# dsp.net
KiCad netlist of a schematic drawn in EAGLE
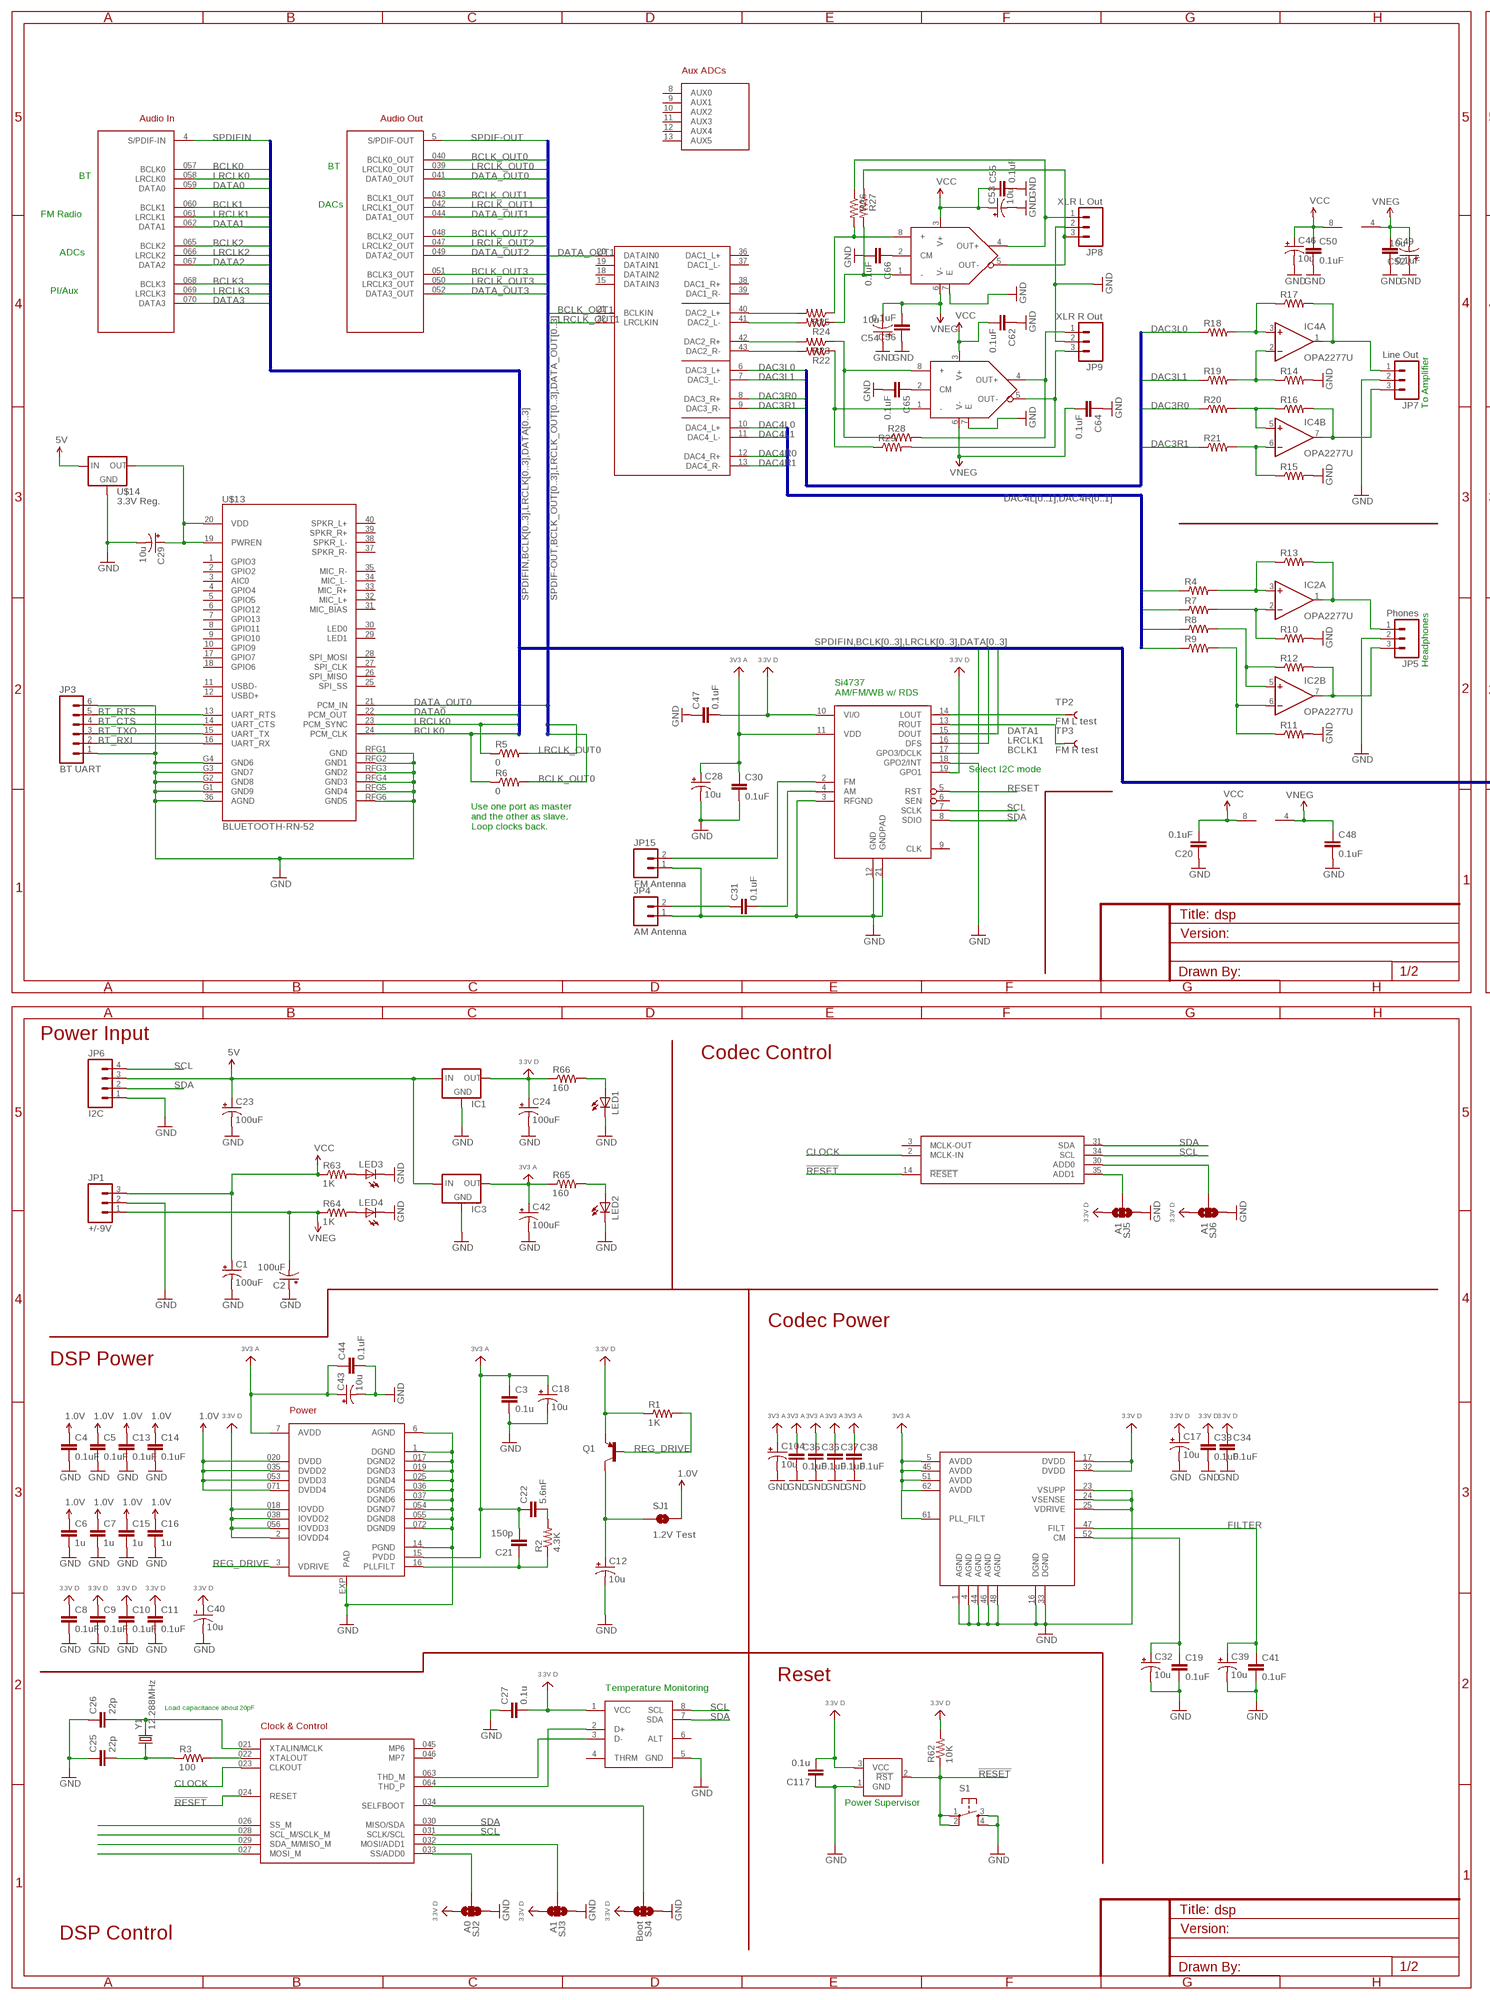
[diagram p0: schematic, sheet 1, part 1 of 2]
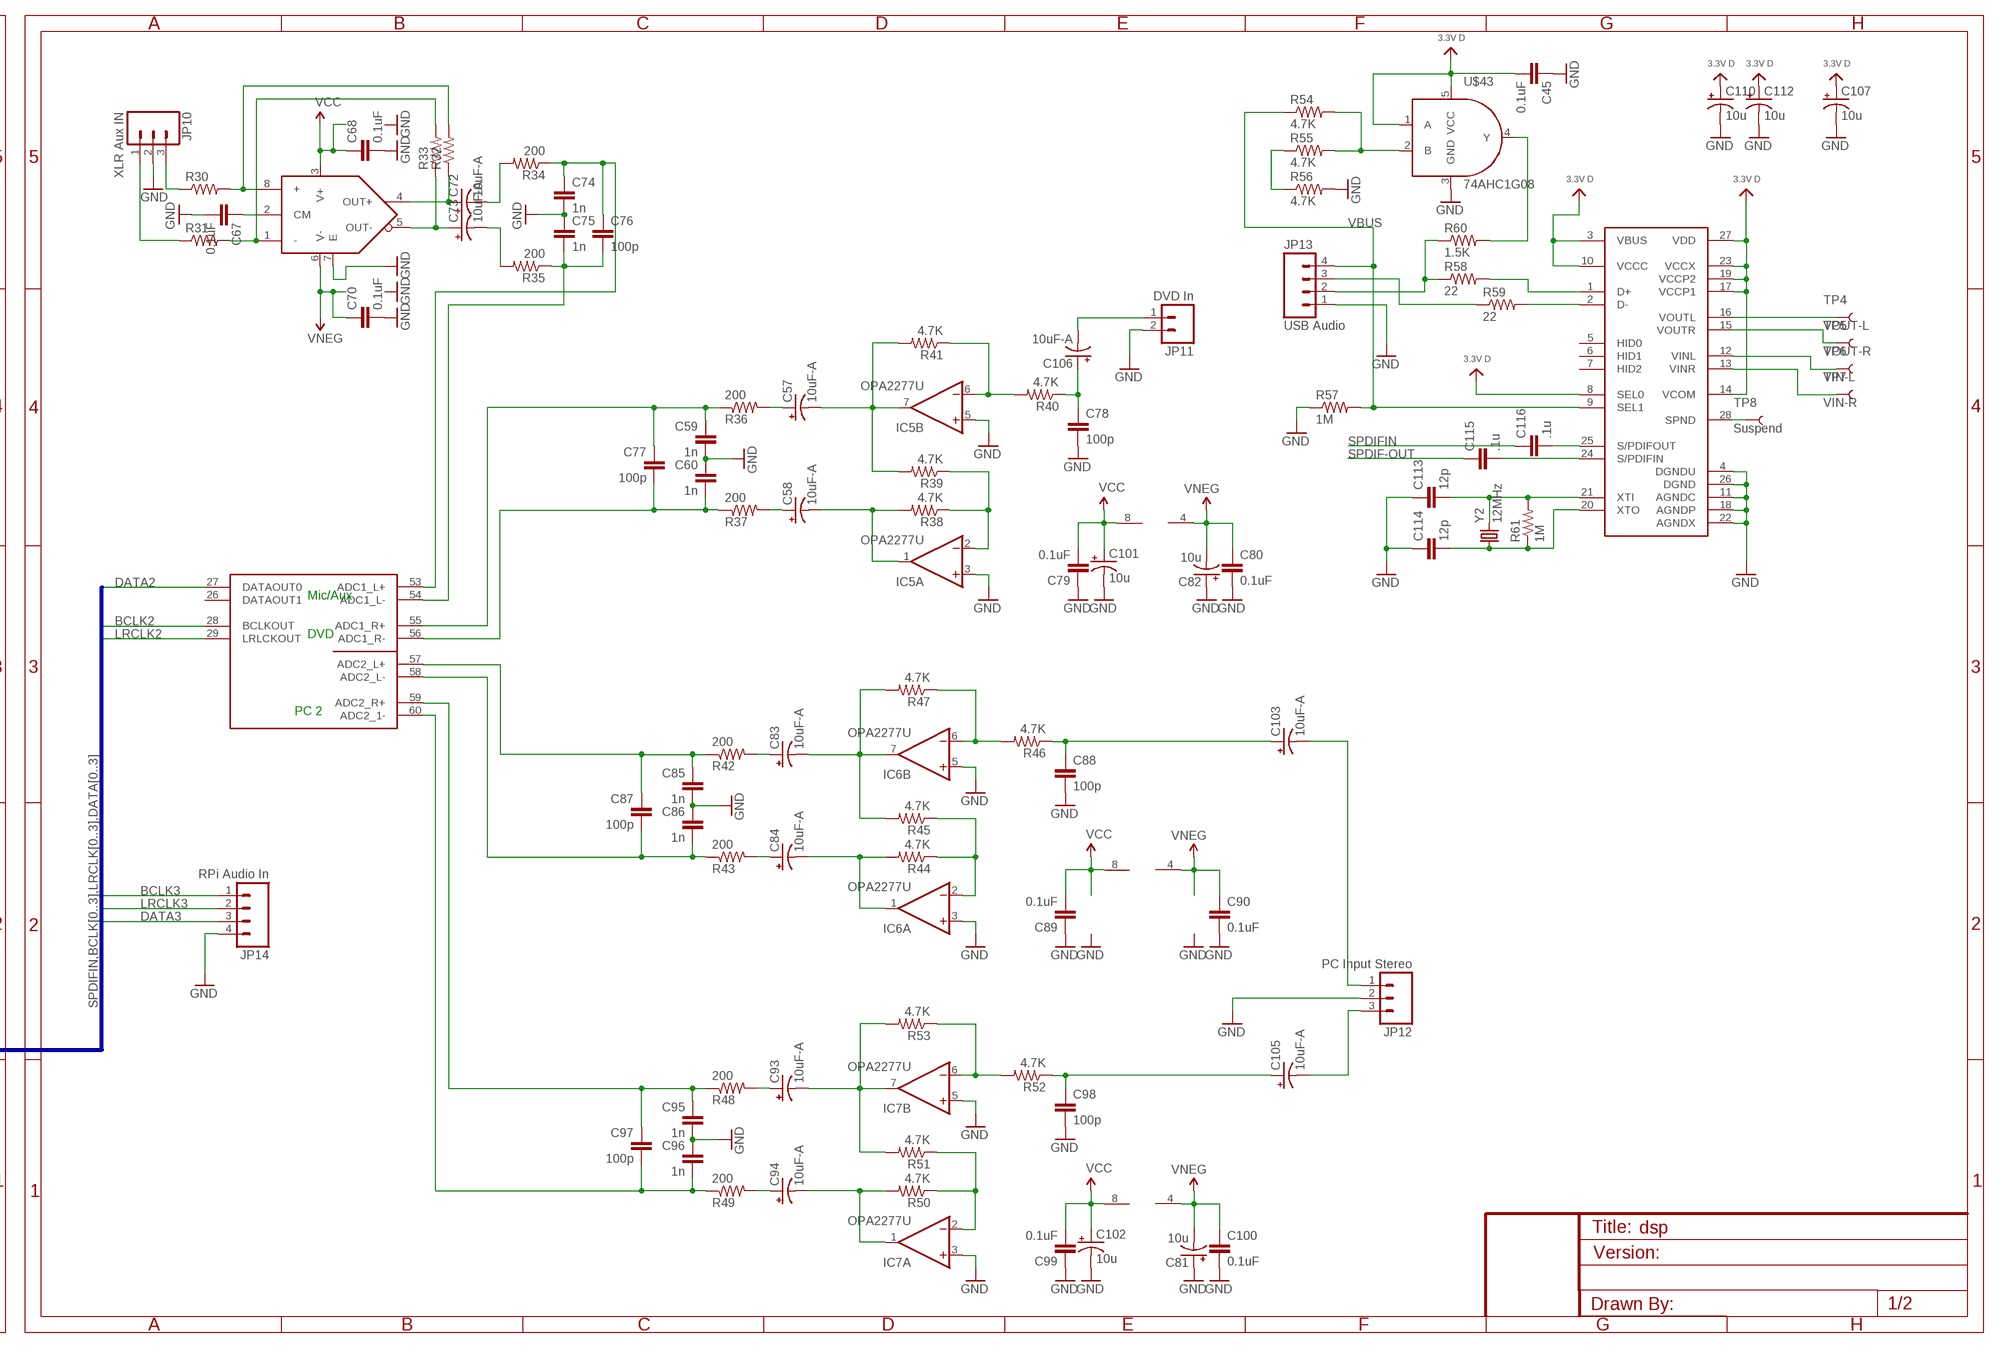
[diagram p1: schematic, sheet 1, part 2 of 2]

(export (version "E")
  (design (tool "Eeschema 10.0.6"))
  (components
    (comp (ref "C1")
      (value "100uF")
      (footprint "eagle-import:CPOL-RADIAL-100UF-25V")
      (libsource (lib "eagle-import") (part "CAP_POLPTH1"))
    )
    (comp (ref "C2")
      (value "100uF")
      (footprint "eagle-import:CPOL-RADIAL-100UF-25V")
      (libsource (lib "eagle-import") (part "CAP_POLPTH1"))
    )
    (comp (ref "C3")
      (value "0.1u")
      (footprint "eagle-import:0603-CAP")
      (libsource (lib "eagle-import") (part "CAP0603-CAP"))
    )
    (comp (ref "C4")
      (value "0.1uF")
      (footprint "eagle-import:0603-CAP")
      (libsource (lib "eagle-import") (part "CAP0603-CAP"))
    )
    (comp (ref "C5")
      (value "0.1uF")
      (footprint "eagle-import:0603-CAP")
      (libsource (lib "eagle-import") (part "CAP0603-CAP"))
    )
    (comp (ref "C6")
      (value "1u")
      (footprint "eagle-import:0603-CAP")
      (libsource (lib "eagle-import") (part "CAP0603-CAP"))
    )
    (comp (ref "C7")
      (value "1u")
      (footprint "eagle-import:0603-CAP")
      (libsource (lib "eagle-import") (part "CAP0603-CAP"))
    )
    (comp (ref "C8")
      (value "0.1uF")
      (footprint "eagle-import:0603-CAP")
      (libsource (lib "eagle-import") (part "CAP0603-CAP"))
    )
    (comp (ref "C9")
      (value "0.1uF")
      (footprint "eagle-import:0603-CAP")
      (libsource (lib "eagle-import") (part "CAP0603-CAP"))
    )
    (comp (ref "C10")
      (value "0.1uF")
      (footprint "eagle-import:0603-CAP")
      (libsource (lib "eagle-import") (part "CAP0603-CAP"))
    )
    (comp (ref "C11")
      (value "0.1uF")
      (footprint "eagle-import:0603-CAP")
      (libsource (lib "eagle-import") (part "CAP0603-CAP"))
    )
    (comp (ref "C12")
      (value "10u")
      (footprint "eagle-import:PANASONIC_B")
      (libsource (lib "eagle-import") (part "CPOL-USB"))
    )
    (comp (ref "C13")
      (value "0.1uF")
      (footprint "eagle-import:0603-CAP")
      (libsource (lib "eagle-import") (part "CAP0603-CAP"))
    )
    (comp (ref "C14")
      (value "0.1uF")
      (footprint "eagle-import:0603-CAP")
      (libsource (lib "eagle-import") (part "CAP0603-CAP"))
    )
    (comp (ref "C15")
      (value "1u")
      (footprint "eagle-import:0603-CAP")
      (libsource (lib "eagle-import") (part "CAP0603-CAP"))
    )
    (comp (ref "C16")
      (value "1u")
      (footprint "eagle-import:0603-CAP")
      (libsource (lib "eagle-import") (part "CAP0603-CAP"))
    )
    (comp (ref "C17")
      (value "10u")
      (footprint "eagle-import:PANASONIC_B")
      (libsource (lib "eagle-import") (part "CPOL-USB"))
    )
    (comp (ref "C18")
      (value "10u")
      (footprint "eagle-import:PANASONIC_B")
      (libsource (lib "eagle-import") (part "CPOL-USB"))
    )
    (comp (ref "C19")
      (value "0.1uF")
      (footprint "eagle-import:0603-CAP")
      (libsource (lib "eagle-import") (part "CAP0603-CAP"))
    )
    (comp (ref "C20")
      (value "0.1uF")
      (footprint "eagle-import:0603-CAP")
      (libsource (lib "eagle-import") (part "CAP0603-CAP"))
    )
    (comp (ref "C21")
      (value "150p")
      (footprint "eagle-import:0603-CAP")
      (libsource (lib "eagle-import") (part "CAP0603-CAP"))
    )
    (comp (ref "C22")
      (value "5.6nF")
      (footprint "eagle-import:0603-CAP")
      (libsource (lib "eagle-import") (part "CAP0603-CAP"))
    )
    (comp (ref "C23")
      (value "100uF")
      (footprint "eagle-import:CPOL-RADIAL-100UF-25V")
      (libsource (lib "eagle-import") (part "CAP_POLPTH1"))
    )
    (comp (ref "C24")
      (value "100uF")
      (footprint "eagle-import:CPOL-RADIAL-100UF-25V")
      (libsource (lib "eagle-import") (part "CAP_POLPTH1"))
    )
    (comp (ref "C25")
      (value "22p")
      (footprint "eagle-import:0603-CAP")
      (libsource (lib "eagle-import") (part "CAP0603-CAP"))
    )
    (comp (ref "C26")
      (value "22p")
      (footprint "eagle-import:0603-CAP")
      (libsource (lib "eagle-import") (part "CAP0603-CAP"))
    )
    (comp (ref "C27")
      (value "0.1u")
      (footprint "eagle-import:0603-CAP")
      (libsource (lib "eagle-import") (part "CAP0603-CAP"))
    )
    (comp (ref "C28")
      (value "10u")
      (footprint "eagle-import:PANASONIC_B")
      (libsource (lib "eagle-import") (part "CPOL-USB"))
    )
    (comp (ref "C29")
      (value "10u")
      (footprint "eagle-import:PANASONIC_B")
      (libsource (lib "eagle-import") (part "CPOL-USB"))
    )
    (comp (ref "C30")
      (value "0.1uF")
      (footprint "eagle-import:0603-CAP")
      (libsource (lib "eagle-import") (part "CAP0603-CAP"))
    )
    (comp (ref "C31")
      (value "0.1uF")
      (footprint "eagle-import:0603-CAP")
      (libsource (lib "eagle-import") (part "CAP0603-CAP"))
    )
    (comp (ref "C32")
      (value "10u")
      (footprint "eagle-import:PANASONIC_B")
      (libsource (lib "eagle-import") (part "CPOL-USB"))
    )
    (comp (ref "C33")
      (value "0.1uF")
      (footprint "eagle-import:0603-CAP")
      (libsource (lib "eagle-import") (part "CAP0603-CAP"))
    )
    (comp (ref "C34")
      (value "0.1uF")
      (footprint "eagle-import:0603-CAP")
      (libsource (lib "eagle-import") (part "CAP0603-CAP"))
    )
    (comp (ref "C35")
      (value "0.1uF")
      (footprint "eagle-import:0603-CAP")
      (libsource (lib "eagle-import") (part "CAP0603-CAP"))
    )
    (comp (ref "C36")
      (value "0.1uF")
      (footprint "eagle-import:0603-CAP")
      (libsource (lib "eagle-import") (part "CAP0603-CAP"))
    )
    (comp (ref "C37")
      (value "0.1uF")
      (footprint "eagle-import:0603-CAP")
      (libsource (lib "eagle-import") (part "CAP0603-CAP"))
    )
    (comp (ref "C38")
      (value "0.1uF")
      (footprint "eagle-import:0603-CAP")
      (libsource (lib "eagle-import") (part "CAP0603-CAP"))
    )
    (comp (ref "C39")
      (value "10u")
      (footprint "eagle-import:PANASONIC_B")
      (libsource (lib "eagle-import") (part "CPOL-USB"))
    )
    (comp (ref "C40")
      (value "10u")
      (footprint "eagle-import:PANASONIC_B")
      (libsource (lib "eagle-import") (part "CPOL-USB"))
    )
    (comp (ref "C41")
      (value "0.1uF")
      (footprint "eagle-import:0603-CAP")
      (libsource (lib "eagle-import") (part "CAP0603-CAP"))
    )
    (comp (ref "C42")
      (value "100uF")
      (footprint "eagle-import:CPOL-RADIAL-100UF-25V")
      (libsource (lib "eagle-import") (part "CAP_POLPTH1"))
    )
    (comp (ref "C43")
      (value "10u")
      (footprint "eagle-import:PANASONIC_B")
      (libsource (lib "eagle-import") (part "CPOL-USB"))
    )
    (comp (ref "C44")
      (value "0.1uF")
      (footprint "eagle-import:0603-CAP")
      (libsource (lib "eagle-import") (part "CAP0603-CAP"))
    )
    (comp (ref "C45")
      (value "0.1uF")
      (footprint "eagle-import:0603-CAP")
      (libsource (lib "eagle-import") (part "CAP0603-CAP"))
    )
    (comp (ref "C46")
      (value "10u")
      (footprint "eagle-import:PANASONIC_B")
      (libsource (lib "eagle-import") (part "CPOL-USB"))
    )
    (comp (ref "C47")
      (value "0.1uF")
      (footprint "eagle-import:0603-CAP")
      (libsource (lib "eagle-import") (part "CAP0603-CAP"))
    )
    (comp (ref "C48")
      (value "0.1uF")
      (footprint "eagle-import:0603-CAP")
      (libsource (lib "eagle-import") (part "CAP0603-CAP"))
    )
    (comp (ref "C49")
      (value "0.1uF")
      (footprint "eagle-import:0603-CAP")
      (libsource (lib "eagle-import") (part "CAP0603-CAP"))
    )
    (comp (ref "C50")
      (value "0.1uF")
      (footprint "eagle-import:0603-CAP")
      (libsource (lib "eagle-import") (part "CAP0603-CAP"))
    )
    (comp (ref "C52")
      (value "10u")
      (footprint "eagle-import:PANASONIC_B")
      (libsource (lib "eagle-import") (part "CPOL-USB"))
    )
    (comp (ref "C53")
      (value "10u")
      (footprint "eagle-import:PANASONIC_B")
      (libsource (lib "eagle-import") (part "CPOL-USB"))
    )
    (comp (ref "C54")
      (value "10u")
      (footprint "eagle-import:PANASONIC_B")
      (libsource (lib "eagle-import") (part "CPOL-USB"))
    )
    (comp (ref "C55")
      (value "0.1uF")
      (footprint "eagle-import:0603-CAP")
      (libsource (lib "eagle-import") (part "CAP0603-CAP"))
    )
    (comp (ref "C56")
      (value "0.1uF")
      (footprint "eagle-import:0603-CAP")
      (libsource (lib "eagle-import") (part "CAP0603-CAP"))
    )
    (comp (ref "C57")
      (value "10uF-A")
      (footprint "eagle-import:PANASONIC_C")
      (libsource (lib "eagle-import") (part "CAP_POLC"))
    )
    (comp (ref "C58")
      (value "10uF-A")
      (footprint "eagle-import:PANASONIC_C")
      (libsource (lib "eagle-import") (part "CAP_POLC"))
    )
    (comp (ref "C59")
      (value "1n")
      (footprint "eagle-import:0603-CAP")
      (libsource (lib "eagle-import") (part "CAP0603-CAP"))
    )
    (comp (ref "C60")
      (value "1n")
      (footprint "eagle-import:0603-CAP")
      (libsource (lib "eagle-import") (part "CAP0603-CAP"))
    )
    (comp (ref "C62")
      (value "0.1uF")
      (footprint "eagle-import:0603-CAP")
      (libsource (lib "eagle-import") (part "CAP0603-CAP"))
    )
    (comp (ref "C64")
      (value "0.1uF")
      (footprint "eagle-import:0603-CAP")
      (libsource (lib "eagle-import") (part "CAP0603-CAP"))
    )
    (comp (ref "C65")
      (value "0.1uF")
      (footprint "eagle-import:0603-CAP")
      (libsource (lib "eagle-import") (part "CAP0603-CAP"))
    )
    (comp (ref "C66")
      (value "0.1uF")
      (footprint "eagle-import:0603-CAP")
      (libsource (lib "eagle-import") (part "CAP0603-CAP"))
    )
    (comp (ref "C67")
      (value "0.1uF")
      (footprint "eagle-import:0603-CAP")
      (libsource (lib "eagle-import") (part "CAP0603-CAP"))
    )
    (comp (ref "C68")
      (value "0.1uF")
      (footprint "eagle-import:0603-CAP")
      (libsource (lib "eagle-import") (part "CAP0603-CAP"))
    )
    (comp (ref "C70")
      (value "0.1uF")
      (footprint "eagle-import:0603-CAP")
      (libsource (lib "eagle-import") (part "CAP0603-CAP"))
    )
    (comp (ref "C72")
      (value "10uF-A")
      (footprint "eagle-import:PANASONIC_C")
      (libsource (lib "eagle-import") (part "CAP_POLC"))
    )
    (comp (ref "C73")
      (value "10uF-A")
      (footprint "eagle-import:PANASONIC_C")
      (libsource (lib "eagle-import") (part "CAP_POLC"))
    )
    (comp (ref "C74")
      (value "1n")
      (footprint "eagle-import:0603-CAP")
      (libsource (lib "eagle-import") (part "CAP0603-CAP"))
    )
    (comp (ref "C75")
      (value "1n")
      (footprint "eagle-import:0603-CAP")
      (libsource (lib "eagle-import") (part "CAP0603-CAP"))
    )
    (comp (ref "C76")
      (value "100p")
      (footprint "eagle-import:0603-CAP")
      (libsource (lib "eagle-import") (part "CAP0603-CAP"))
    )
    (comp (ref "C77")
      (value "100p")
      (footprint "eagle-import:0603-CAP")
      (libsource (lib "eagle-import") (part "CAP0603-CAP"))
    )
    (comp (ref "C78")
      (value "100p")
      (footprint "eagle-import:0603-CAP")
      (libsource (lib "eagle-import") (part "CAP0603-CAP"))
    )
    (comp (ref "C79")
      (value "0.1uF")
      (footprint "eagle-import:0603-CAP")
      (libsource (lib "eagle-import") (part "CAP0603-CAP"))
    )
    (comp (ref "C80")
      (value "0.1uF")
      (footprint "eagle-import:0603-CAP")
      (libsource (lib "eagle-import") (part "CAP0603-CAP"))
    )
    (comp (ref "C81")
      (value "10u")
      (footprint "eagle-import:PANASONIC_B")
      (libsource (lib "eagle-import") (part "CPOL-USB"))
    )
    (comp (ref "C82")
      (value "10u")
      (footprint "eagle-import:PANASONIC_B")
      (libsource (lib "eagle-import") (part "CPOL-USB"))
    )
    (comp (ref "C83")
      (value "10uF-A")
      (footprint "eagle-import:PANASONIC_C")
      (libsource (lib "eagle-import") (part "CAP_POLC"))
    )
    (comp (ref "C84")
      (value "10uF-A")
      (footprint "eagle-import:PANASONIC_C")
      (libsource (lib "eagle-import") (part "CAP_POLC"))
    )
    (comp (ref "C85")
      (value "1n")
      (footprint "eagle-import:0603-CAP")
      (libsource (lib "eagle-import") (part "CAP0603-CAP"))
    )
    (comp (ref "C86")
      (value "1n")
      (footprint "eagle-import:0603-CAP")
      (libsource (lib "eagle-import") (part "CAP0603-CAP"))
    )
    (comp (ref "C87")
      (value "100p")
      (footprint "eagle-import:0603-CAP")
      (libsource (lib "eagle-import") (part "CAP0603-CAP"))
    )
    (comp (ref "C88")
      (value "100p")
      (footprint "eagle-import:0603-CAP")
      (libsource (lib "eagle-import") (part "CAP0603-CAP"))
    )
    (comp (ref "C89")
      (value "0.1uF")
      (footprint "eagle-import:0603-CAP")
      (libsource (lib "eagle-import") (part "CAP0603-CAP"))
    )
    (comp (ref "C90")
      (value "0.1uF")
      (footprint "eagle-import:0603-CAP")
      (libsource (lib "eagle-import") (part "CAP0603-CAP"))
    )
    (comp (ref "C93")
      (value "10uF-A")
      (footprint "eagle-import:PANASONIC_C")
      (libsource (lib "eagle-import") (part "CAP_POLC"))
    )
    (comp (ref "C94")
      (value "10uF-A")
      (footprint "eagle-import:PANASONIC_C")
      (libsource (lib "eagle-import") (part "CAP_POLC"))
    )
    (comp (ref "C95")
      (value "1n")
      (footprint "eagle-import:0603-CAP")
      (libsource (lib "eagle-import") (part "CAP0603-CAP"))
    )
    (comp (ref "C96")
      (value "1n")
      (footprint "eagle-import:0603-CAP")
      (libsource (lib "eagle-import") (part "CAP0603-CAP"))
    )
    (comp (ref "C97")
      (value "100p")
      (footprint "eagle-import:0603-CAP")
      (libsource (lib "eagle-import") (part "CAP0603-CAP"))
    )
    (comp (ref "C98")
      (value "100p")
      (footprint "eagle-import:0603-CAP")
      (libsource (lib "eagle-import") (part "CAP0603-CAP"))
    )
    (comp (ref "C99")
      (value "0.1uF")
      (footprint "eagle-import:0603-CAP")
      (libsource (lib "eagle-import") (part "CAP0603-CAP"))
    )
    (comp (ref "C100")
      (value "0.1uF")
      (footprint "eagle-import:0603-CAP")
      (libsource (lib "eagle-import") (part "CAP0603-CAP"))
    )
    (comp (ref "C101")
      (value "10u")
      (footprint "eagle-import:PANASONIC_B")
      (libsource (lib "eagle-import") (part "CPOL-USB"))
    )
    (comp (ref "C102")
      (value "10u")
      (footprint "eagle-import:PANASONIC_B")
      (libsource (lib "eagle-import") (part "CPOL-USB"))
    )
    (comp (ref "C103")
      (value "10uF-A")
      (footprint "eagle-import:PANASONIC_C")
      (libsource (lib "eagle-import") (part "CAP_POLC"))
    )
    (comp (ref "C104")
      (value "10u")
      (footprint "eagle-import:PANASONIC_B")
      (libsource (lib "eagle-import") (part "CPOL-USB"))
    )
    (comp (ref "C105")
      (value "10uF-A")
      (footprint "eagle-import:PANASONIC_C")
      (libsource (lib "eagle-import") (part "CAP_POLC"))
    )
    (comp (ref "C106")
      (value "10uF-A")
      (footprint "eagle-import:PANASONIC_C")
      (libsource (lib "eagle-import") (part "CAP_POLC"))
    )
    (comp (ref "C107")
      (value "10u")
      (footprint "eagle-import:PANASONIC_B")
      (libsource (lib "eagle-import") (part "CPOL-USB"))
    )
    (comp (ref "C110")
      (value "10u")
      (footprint "eagle-import:PANASONIC_B")
      (libsource (lib "eagle-import") (part "CPOL-USB"))
    )
    (comp (ref "C112")
      (value "10u")
      (footprint "eagle-import:PANASONIC_B")
      (libsource (lib "eagle-import") (part "CPOL-USB"))
    )
    (comp (ref "C113")
      (value "12p")
      (footprint "eagle-import:0603-CAP")
      (libsource (lib "eagle-import") (part "CAP0603-CAP"))
    )
    (comp (ref "C114")
      (value "12p")
      (footprint "eagle-import:0603-CAP")
      (libsource (lib "eagle-import") (part "CAP0603-CAP"))
    )
    (comp (ref "C115")
      (value ".1u")
      (footprint "eagle-import:0603-CAP")
      (libsource (lib "eagle-import") (part "CAP0603-CAP"))
    )
    (comp (ref "C116")
      (value ".1u")
      (footprint "eagle-import:0603-CAP")
      (libsource (lib "eagle-import") (part "CAP0603-CAP"))
    )
    (comp (ref "C117")
      (value "0.1u")
      (footprint "eagle-import:0603-CAP")
      (libsource (lib "eagle-import") (part "CAP0603-CAP"))
    )
    (comp (ref "IC1")
      (value "V_REG_78XXSINK")
      (footprint "eagle-import:TO220-IGO")
      (libsource (lib "eagle-import") (part "V_REG_78XXSINK"))
    )
    (comp (ref "IC2")
      (value "OPA2277U")
      (footprint "eagle-import:SO08")
      (libsource (lib "eagle-import") (part "OPA2277U"))
    )
    (comp (ref "IC3")
      (value "V_REG_78XXSINK")
      (footprint "eagle-import:TO220-IGO")
      (libsource (lib "eagle-import") (part "V_REG_78XXSINK"))
    )
    (comp (ref "IC4")
      (value "OPA2277U")
      (footprint "eagle-import:SO08")
      (libsource (lib "eagle-import") (part "OPA2277U"))
    )
    (comp (ref "IC5")
      (value "OPA2277U")
      (footprint "eagle-import:SO08")
      (libsource (lib "eagle-import") (part "OPA2277U"))
    )
    (comp (ref "IC6")
      (value "OPA2277U")
      (footprint "eagle-import:SO08")
      (libsource (lib "eagle-import") (part "OPA2277U"))
    )
    (comp (ref "IC7")
      (value "OPA2277U")
      (footprint "eagle-import:SO08")
      (libsource (lib "eagle-import") (part "OPA2277U"))
    )
    (comp (ref "JP1")
      (value "+/-9V")
      (footprint "eagle-import:MOLEX-1X3")
      (libsource (lib "eagle-import") (part "M03POLAR"))
    )
    (comp (ref "JP3")
      (value "BT UART")
      (footprint "eagle-import:MOLEX-1X6")
      (libsource (lib "eagle-import") (part "M06POLAR"))
    )
    (comp (ref "JP4")
      (value "AM Antenna")
      (footprint "eagle-import:1X02")
      (libsource (lib "eagle-import") (part "M02PTH"))
    )
    (comp (ref "JP5")
      (value "Phones")
      (footprint "eagle-import:MOLEX-1X3")
      (libsource (lib "eagle-import") (part "M03POLAR"))
    )
    (comp (ref "JP6")
      (value "I2C")
      (footprint "eagle-import:MOLEX-1X4")
      (libsource (lib "eagle-import") (part "M04POLAR"))
    )
    (comp (ref "JP7")
      (value "Line Out")
      (footprint "eagle-import:MOLEX-1X3")
      (libsource (lib "eagle-import") (part "M03POLAR"))
    )
    (comp (ref "JP8")
      (value "XLR L Out")
      (footprint "eagle-import:MOLEX-1X3")
      (libsource (lib "eagle-import") (part "M03POLAR"))
    )
    (comp (ref "JP9")
      (value "XLR R Out")
      (footprint "eagle-import:MOLEX-1X3")
      (libsource (lib "eagle-import") (part "M03POLAR"))
    )
    (comp (ref "JP10")
      (value "XLR Aux IN")
      (footprint "eagle-import:MOLEX-1X3")
      (libsource (lib "eagle-import") (part "M03POLAR"))
    )
    (comp (ref "JP11")
      (value "DVD In")
      (footprint "eagle-import:MOLEX-1X2")
      (libsource (lib "eagle-import") (part "M02POLAR"))
    )
    (comp (ref "JP12")
      (value "PC Input Stereo")
      (footprint "eagle-import:MOLEX-1X3")
      (libsource (lib "eagle-import") (part "M03POLAR"))
    )
    (comp (ref "JP13")
      (value "USB Audio")
      (footprint "eagle-import:MOLEX-1X4")
      (libsource (lib "eagle-import") (part "M04POLAR"))
    )
    (comp (ref "JP14")
      (value "RPi Audio In")
      (footprint "eagle-import:MOLEX-1X4")
      (libsource (lib "eagle-import") (part "M04POLAR"))
    )
    (comp (ref "JP15")
      (value "FM Antenna")
      (footprint "eagle-import:1X02")
      (libsource (lib "eagle-import") (part "M02PTH"))
    )
    (comp (ref "LED1")
      (value "LED1206")
      (footprint "eagle-import:LED-1206")
      (libsource (lib "eagle-import") (part "LED1206"))
    )
    (comp (ref "LED2")
      (value "LED1206")
      (footprint "eagle-import:LED-1206")
      (libsource (lib "eagle-import") (part "LED1206"))
    )
    (comp (ref "LED3")
      (value "LED1206")
      (footprint "eagle-import:LED-1206")
      (libsource (lib "eagle-import") (part "LED1206"))
    )
    (comp (ref "LED4")
      (value "LED1206")
      (footprint "eagle-import:LED-1206")
      (libsource (lib "eagle-import") (part "LED1206"))
    )
    (comp (ref "Q1")
      (value "TRANSISTOR_PNPSMD")
      (footprint "eagle-import:SOT23-3")
      (libsource (lib "eagle-import") (part "TRANSISTOR_PNPSMD"))
    )
    (comp (ref "R1")
      (value "1K")
      (footprint "eagle-import:1206")
      (libsource (lib "eagle-import") (part "RESISTOR1206"))
    )
    (comp (ref "R2")
      (value "4.3K")
      (footprint "eagle-import:1206")
      (libsource (lib "eagle-import") (part "RESISTOR1206"))
    )
    (comp (ref "R3")
      (value "100")
      (footprint "eagle-import:1206")
      (libsource (lib "eagle-import") (part "RESISTOR1206"))
    )
    (comp (ref "R4")
      (value "RESISTOR1206")
      (footprint "eagle-import:1206")
      (libsource (lib "eagle-import") (part "RESISTOR1206"))
    )
    (comp (ref "R5")
      (value "0")
      (footprint "eagle-import:1206")
      (libsource (lib "eagle-import") (part "RESISTOR1206"))
    )
    (comp (ref "R6")
      (value "0")
      (footprint "eagle-import:1206")
      (libsource (lib "eagle-import") (part "RESISTOR1206"))
    )
    (comp (ref "R7")
      (value "RESISTOR1206")
      (footprint "eagle-import:1206")
      (libsource (lib "eagle-import") (part "RESISTOR1206"))
    )
    (comp (ref "R8")
      (value "RESISTOR1206")
      (footprint "eagle-import:1206")
      (libsource (lib "eagle-import") (part "RESISTOR1206"))
    )
    (comp (ref "R9")
      (value "RESISTOR1206")
      (footprint "eagle-import:1206")
      (libsource (lib "eagle-import") (part "RESISTOR1206"))
    )
    (comp (ref "R10")
      (value "RESISTOR1206")
      (footprint "eagle-import:1206")
      (libsource (lib "eagle-import") (part "RESISTOR1206"))
    )
    (comp (ref "R11")
      (value "RESISTOR1206")
      (footprint "eagle-import:1206")
      (libsource (lib "eagle-import") (part "RESISTOR1206"))
    )
    (comp (ref "R12")
      (value "RESISTOR1206")
      (footprint "eagle-import:1206")
      (libsource (lib "eagle-import") (part "RESISTOR1206"))
    )
    (comp (ref "R13")
      (value "RESISTOR1206")
      (footprint "eagle-import:1206")
      (libsource (lib "eagle-import") (part "RESISTOR1206"))
    )
    (comp (ref "R14")
      (value "RESISTOR1206")
      (footprint "eagle-import:1206")
      (libsource (lib "eagle-import") (part "RESISTOR1206"))
    )
    (comp (ref "R15")
      (value "RESISTOR1206")
      (footprint "eagle-import:1206")
      (libsource (lib "eagle-import") (part "RESISTOR1206"))
    )
    (comp (ref "R16")
      (value "RESISTOR1206")
      (footprint "eagle-import:1206")
      (libsource (lib "eagle-import") (part "RESISTOR1206"))
    )
    (comp (ref "R17")
      (value "RESISTOR1206")
      (footprint "eagle-import:1206")
      (libsource (lib "eagle-import") (part "RESISTOR1206"))
    )
    (comp (ref "R18")
      (value "RESISTOR1206")
      (footprint "eagle-import:1206")
      (libsource (lib "eagle-import") (part "RESISTOR1206"))
    )
    (comp (ref "R19")
      (value "RESISTOR1206")
      (footprint "eagle-import:1206")
      (libsource (lib "eagle-import") (part "RESISTOR1206"))
    )
    (comp (ref "R20")
      (value "RESISTOR1206")
      (footprint "eagle-import:1206")
      (libsource (lib "eagle-import") (part "RESISTOR1206"))
    )
    (comp (ref "R21")
      (value "RESISTOR1206")
      (footprint "eagle-import:1206")
      (libsource (lib "eagle-import") (part "RESISTOR1206"))
    )
    (comp (ref "R22")
      (value "RESISTOR1206")
      (footprint "eagle-import:1206")
      (libsource (lib "eagle-import") (part "RESISTOR1206"))
    )
    (comp (ref "R23")
      (value "RESISTOR1206")
      (footprint "eagle-import:1206")
      (libsource (lib "eagle-import") (part "RESISTOR1206"))
    )
    (comp (ref "R24")
      (value "RESISTOR1206")
      (footprint "eagle-import:1206")
      (libsource (lib "eagle-import") (part "RESISTOR1206"))
    )
    (comp (ref "R25")
      (value "RESISTOR1206")
      (footprint "eagle-import:1206")
      (libsource (lib "eagle-import") (part "RESISTOR1206"))
    )
    (comp (ref "R26")
      (value "RESISTOR1206")
      (footprint "eagle-import:1206")
      (libsource (lib "eagle-import") (part "RESISTOR1206"))
    )
    (comp (ref "R27")
      (value "RESISTOR1206")
      (footprint "eagle-import:1206")
      (libsource (lib "eagle-import") (part "RESISTOR1206"))
    )
    (comp (ref "R28")
      (value "RESISTOR1206")
      (footprint "eagle-import:1206")
      (libsource (lib "eagle-import") (part "RESISTOR1206"))
    )
    (comp (ref "R29")
      (value "RESISTOR1206")
      (footprint "eagle-import:1206")
      (libsource (lib "eagle-import") (part "RESISTOR1206"))
    )
    (comp (ref "R30")
      (value "RESISTOR1206")
      (footprint "eagle-import:1206")
      (libsource (lib "eagle-import") (part "RESISTOR1206"))
    )
    (comp (ref "R31")
      (value "RESISTOR1206")
      (footprint "eagle-import:1206")
      (libsource (lib "eagle-import") (part "RESISTOR1206"))
    )
    (comp (ref "R32")
      (value "RESISTOR1206")
      (footprint "eagle-import:1206")
      (libsource (lib "eagle-import") (part "RESISTOR1206"))
    )
    (comp (ref "R33")
      (value "RESISTOR1206")
      (footprint "eagle-import:1206")
      (libsource (lib "eagle-import") (part "RESISTOR1206"))
    )
    (comp (ref "R34")
      (value "200")
      (footprint "eagle-import:1206")
      (libsource (lib "eagle-import") (part "RESISTOR1206"))
    )
    (comp (ref "R35")
      (value "200")
      (footprint "eagle-import:1206")
      (libsource (lib "eagle-import") (part "RESISTOR1206"))
    )
    (comp (ref "R36")
      (value "200")
      (footprint "eagle-import:1206")
      (libsource (lib "eagle-import") (part "RESISTOR1206"))
    )
    (comp (ref "R37")
      (value "200")
      (footprint "eagle-import:1206")
      (libsource (lib "eagle-import") (part "RESISTOR1206"))
    )
    (comp (ref "R38")
      (value "4.7K")
      (footprint "eagle-import:1206")
      (libsource (lib "eagle-import") (part "RESISTOR1206"))
    )
    (comp (ref "R39")
      (value "4.7K")
      (footprint "eagle-import:1206")
      (libsource (lib "eagle-import") (part "RESISTOR1206"))
    )
    (comp (ref "R40")
      (value "4.7K")
      (footprint "eagle-import:1206")
      (libsource (lib "eagle-import") (part "RESISTOR1206"))
    )
    (comp (ref "R41")
      (value "4.7K")
      (footprint "eagle-import:1206")
      (libsource (lib "eagle-import") (part "RESISTOR1206"))
    )
    (comp (ref "R42")
      (value "200")
      (footprint "eagle-import:1206")
      (libsource (lib "eagle-import") (part "RESISTOR1206"))
    )
    (comp (ref "R43")
      (value "200")
      (footprint "eagle-import:1206")
      (libsource (lib "eagle-import") (part "RESISTOR1206"))
    )
    (comp (ref "R44")
      (value "4.7K")
      (footprint "eagle-import:1206")
      (libsource (lib "eagle-import") (part "RESISTOR1206"))
    )
    (comp (ref "R45")
      (value "4.7K")
      (footprint "eagle-import:1206")
      (libsource (lib "eagle-import") (part "RESISTOR1206"))
    )
    (comp (ref "R46")
      (value "4.7K")
      (footprint "eagle-import:1206")
      (libsource (lib "eagle-import") (part "RESISTOR1206"))
    )
    (comp (ref "R47")
      (value "4.7K")
      (footprint "eagle-import:1206")
      (libsource (lib "eagle-import") (part "RESISTOR1206"))
    )
    (comp (ref "R48")
      (value "200")
      (footprint "eagle-import:1206")
      (libsource (lib "eagle-import") (part "RESISTOR1206"))
    )
    (comp (ref "R49")
      (value "200")
      (footprint "eagle-import:1206")
      (libsource (lib "eagle-import") (part "RESISTOR1206"))
    )
    (comp (ref "R50")
      (value "4.7K")
      (footprint "eagle-import:1206")
      (libsource (lib "eagle-import") (part "RESISTOR1206"))
    )
    (comp (ref "R51")
      (value "4.7K")
      (footprint "eagle-import:1206")
      (libsource (lib "eagle-import") (part "RESISTOR1206"))
    )
    (comp (ref "R52")
      (value "4.7K")
      (footprint "eagle-import:1206")
      (libsource (lib "eagle-import") (part "RESISTOR1206"))
    )
    (comp (ref "R53")
      (value "4.7K")
      (footprint "eagle-import:1206")
      (libsource (lib "eagle-import") (part "RESISTOR1206"))
    )
    (comp (ref "R54")
      (value "4.7K")
      (footprint "eagle-import:1206")
      (libsource (lib "eagle-import") (part "RESISTOR1206"))
    )
    (comp (ref "R55")
      (value "4.7K")
      (footprint "eagle-import:1206")
      (libsource (lib "eagle-import") (part "RESISTOR1206"))
    )
    (comp (ref "R56")
      (value "4.7K")
      (footprint "eagle-import:1206")
      (libsource (lib "eagle-import") (part "RESISTOR1206"))
    )
    (comp (ref "R57")
      (value "1M")
      (footprint "eagle-import:1206")
      (libsource (lib "eagle-import") (part "RESISTOR1206"))
    )
    (comp (ref "R58")
      (value "22")
      (footprint "eagle-import:1206")
      (libsource (lib "eagle-import") (part "RESISTOR1206"))
    )
    (comp (ref "R59")
      (value "22")
      (footprint "eagle-import:1206")
      (libsource (lib "eagle-import") (part "RESISTOR1206"))
    )
    (comp (ref "R60")
      (value "1.5K")
      (footprint "eagle-import:1206")
      (libsource (lib "eagle-import") (part "RESISTOR1206"))
    )
    (comp (ref "R61")
      (value "1M")
      (footprint "eagle-import:1206")
      (libsource (lib "eagle-import") (part "RESISTOR1206"))
    )
    (comp (ref "R62")
      (value "10K")
      (footprint "eagle-import:1206")
      (libsource (lib "eagle-import") (part "RESISTOR1206"))
    )
    (comp (ref "R63")
      (value "1K")
      (footprint "eagle-import:1206")
      (libsource (lib "eagle-import") (part "RESISTOR1206"))
    )
    (comp (ref "R64")
      (value "1K")
      (footprint "eagle-import:1206")
      (libsource (lib "eagle-import") (part "RESISTOR1206"))
    )
    (comp (ref "R65")
      (value "160")
      (footprint "eagle-import:1206")
      (libsource (lib "eagle-import") (part "RESISTOR1206"))
    )
    (comp (ref "R66")
      (value "160")
      (footprint "eagle-import:1206")
      (libsource (lib "eagle-import") (part "RESISTOR1206"))
    )
    (comp (ref "S1")
      (value "TAC_SWITCHPTH")
      (footprint "eagle-import:TACTILE-PTH")
      (libsource (lib "eagle-import") (part "TAC_SWITCHPTH"))
    )
    (comp (ref "SJ1")
      (value "1.2V Test")
      (footprint "eagle-import:SJ_2S-NO")
      (libsource (lib "eagle-import") (part "SOLDERJUMPERNO"))
    )
    (comp (ref "SJ2")
      (value "A0")
      (footprint "eagle-import:SJ_3")
      (libsource (lib "eagle-import") (part "SOLDERJUMPER_2WAYS"))
    )
    (comp (ref "SJ3")
      (value "A1")
      (footprint "eagle-import:SJ_3")
      (libsource (lib "eagle-import") (part "SOLDERJUMPER_2WAYS"))
    )
    (comp (ref "SJ4")
      (value "Boot")
      (footprint "eagle-import:SJ_3")
      (libsource (lib "eagle-import") (part "SOLDERJUMPER_2WAYS"))
    )
    (comp (ref "SJ5")
      (value "A1")
      (footprint "eagle-import:SJ_3")
      (libsource (lib "eagle-import") (part "SOLDERJUMPER_2WAYS"))
    )
    (comp (ref "SJ6")
      (value "A1")
      (footprint "eagle-import:SJ_3")
      (libsource (lib "eagle-import") (part "SOLDERJUMPER_2WAYS"))
    )
    (comp (ref "TP2")
      (value "FM L test")
      (footprint "eagle-import:PAD.03X.03")
      (libsource (lib "eagle-import") (part "TEST-POINT3"))
    )
    (comp (ref "TP3")
      (value "FM R test")
      (footprint "eagle-import:PAD.03X.03")
      (libsource (lib "eagle-import") (part "TEST-POINT3"))
    )
    (comp (ref "TP4")
      (value "VOUT-L")
      (footprint "eagle-import:PAD.03X.03")
      (libsource (lib "eagle-import") (part "TEST-POINT3"))
    )
    (comp (ref "TP5")
      (value "VOUT-R")
      (footprint "eagle-import:PAD.03X.03")
      (libsource (lib "eagle-import") (part "TEST-POINT3"))
    )
    (comp (ref "TP6")
      (value "VIN-L")
      (footprint "eagle-import:PAD.03X.03")
      (libsource (lib "eagle-import") (part "TEST-POINT3"))
    )
    (comp (ref "TP7")
      (value "VIN-R")
      (footprint "eagle-import:PAD.03X.03")
      (libsource (lib "eagle-import") (part "TEST-POINT3"))
    )
    (comp (ref "TP8")
      (value "Suspend")
      (footprint "eagle-import:PAD.03X.03")
      (libsource (lib "eagle-import") (part "TEST-POINT3"))
    )
    (comp (ref "U$1")
      (value "ADAU1451")
      (footprint "eagle-import:LFCSP-72")
      (libsource (lib "eagle-import") (part "ADAU1451"))
    )
    (comp (ref "U$8")
      (value "ADM1032")
      (footprint "eagle-import:MSOP-8")
      (libsource (lib "eagle-import") (part "ADM1032"))
    )
    (comp (ref "U$13")
      (value "BLUETOOTH-RN-52")
      (footprint "eagle-import:RN-52")
      (libsource (lib "eagle-import") (part "BLUETOOTH-RN-52"))
    )
    (comp (ref "U$14")
      (value "3.3V Reg.")
      (footprint "eagle-import:SOT223")
      (libsource (lib "eagle-import") (part "V_REG_MIC2920"))
    )
    (comp (ref "U$15")
      (value "SI4736/37/38/39")
      (footprint "eagle-import:QFN-16")
      (libsource (lib "eagle-import") (part "SI4736/37/38/39"))
    )
    (comp (ref "U$17")
      (value "AD1937")
      (footprint "eagle-import:LQFP-64")
      (libsource (lib "eagle-import") (part "AD1937"))
    )
    (comp (ref "U$35")
      (value "LME49724")
      (footprint "eagle-import:SOIC-8")
      (libsource (lib "eagle-import") (part "LME49724"))
    )
    (comp (ref "U$38")
      (value "LME49724")
      (footprint "eagle-import:SOIC-8")
      (libsource (lib "eagle-import") (part "LME49724"))
    )
    (comp (ref "U$39")
      (value "LME49724")
      (footprint "eagle-import:SOIC-8")
      (libsource (lib "eagle-import") (part "LME49724"))
    )
    (comp (ref "U$40")
      (value "PCM2903")
      (footprint "eagle-import:SSOP-28")
      (libsource (lib "eagle-import") (part "PCM2903"))
    )
    (comp (ref "U$43")
      (value "74AHC1G08")
      (footprint "eagle-import:SOT23-5")
      (libsource (lib "eagle-import") (part "74AHC1G08"))
    )
    (comp (ref "U$52")
      (value "TLV803")
      (footprint "eagle-import:SOT23")
      (libsource (lib "eagle-import") (part "TLV803"))
    )
    (comp (ref "Y1")
      (value "12.288MHz")
      (footprint "eagle-import:HC49U-V")
      (libsource (lib "eagle-import") (part "CRYSTALHC49UV"))
    )
    (comp (ref "Y2")
      (value "12MHz")
      (footprint "eagle-import:HC49U-V")
      (libsource (lib "eagle-import") (part "CRYSTALHC49UV"))
    )
  )
  (nets
    (net (code "4") (name "1.0V") (class "Default")
      (node (ref "C13") (pin "1") (pinfunction "1_1") (pintype "passive"))
      (node (ref "C14") (pin "1") (pinfunction "1_1") (pintype "passive"))
      (node (ref "C15") (pin "1") (pinfunction "1_1") (pintype "passive"))
      (node (ref "C16") (pin "1") (pinfunction "1_1") (pintype "passive"))
      (node (ref "C4") (pin "1") (pinfunction "1_1") (pintype "passive"))
      (node (ref "C5") (pin "1") (pinfunction "1_1") (pintype "passive"))
      (node (ref "C6") (pin "1") (pinfunction "1_1") (pintype "passive"))
      (node (ref "C7") (pin "1") (pinfunction "1_1") (pintype "passive"))
      (node (ref "SJ1") (pin "2") (pinfunction "2_2") (pintype "passive"))
      (node (ref "U$1") (pin "020") (pinfunction "DVDD_020") (pintype "bidirectional"))
      (node (ref "U$1") (pin "035") (pinfunction "DVDD2_035") (pintype "bidirectional"))
      (node (ref "U$1") (pin "053") (pinfunction "DVDD3_053") (pintype "bidirectional"))
      (node (ref "U$1") (pin "071") (pinfunction "DVDD4_071") (pintype "bidirectional"))
    )
    (net (code "5") (name "3.3V_A") (class "Default")
      (node (ref "C104") (pin "+") (pinfunction "+_+") (pintype "passive"))
      (node (ref "C18") (pin "+") (pinfunction "+_+") (pintype "passive"))
      (node (ref "C21") (pin "2") (pinfunction "2_2") (pintype "passive"))
      (node (ref "C22") (pin "1") (pinfunction "1_1") (pintype "passive"))
      (node (ref "C28") (pin "+") (pinfunction "+_+") (pintype "passive"))
      (node (ref "C3") (pin "1") (pinfunction "1_1") (pintype "passive"))
      (node (ref "C30") (pin "1") (pinfunction "1_1") (pintype "passive"))
      (node (ref "C35") (pin "1") (pinfunction "1_1") (pintype "passive"))
      (node (ref "C36") (pin "1") (pinfunction "1_1") (pintype "passive"))
      (node (ref "C37") (pin "1") (pinfunction "1_1") (pintype "passive"))
      (node (ref "C38") (pin "1") (pinfunction "1_1") (pintype "passive"))
      (node (ref "C42") (pin "1") (pinfunction "+_1") (pintype "passive"))
      (node (ref "C43") (pin "+") (pinfunction "+_+") (pintype "passive"))
      (node (ref "C44") (pin "1") (pinfunction "1_1") (pintype "passive"))
      (node (ref "IC3") (pin "OUT") (pinfunction "OUT_OUT") (pintype "output"))
      (node (ref "R65") (pin "1") (pinfunction "1_1") (pintype "passive"))
      (node (ref "U$1") (pin "15") (pinfunction "PVDD_15") (pintype "bidirectional"))
      (node (ref "U$1") (pin "7") (pinfunction "AVDD_7") (pintype "bidirectional"))
      (node (ref "U$15") (pin "11") (pinfunction "VDD_11") (pintype "bidirectional"))
      (node (ref "U$17") (pin "45") (pinfunction "AVDD_45") (pintype "bidirectional"))
      (node (ref "U$17") (pin "5") (pinfunction "AVDD_5") (pintype "bidirectional"))
      (node (ref "U$17") (pin "51") (pinfunction "AVDD_51") (pintype "bidirectional"))
      (node (ref "U$17") (pin "61") (pinfunction "PLL_FILT_61") (pintype "bidirectional"))
      (node (ref "U$17") (pin "62") (pinfunction "AVDD_62") (pintype "bidirectional"))
    )
    (net (code "6") (name "3V3_D") (class "Default")
      (node (ref "C10") (pin "1") (pinfunction "1_1") (pintype "passive"))
      (node (ref "C107") (pin "+") (pinfunction "+_+") (pintype "passive"))
      (node (ref "C11") (pin "1") (pinfunction "1_1") (pintype "passive"))
      (node (ref "C110") (pin "+") (pinfunction "+_+") (pintype "passive"))
      (node (ref "C112") (pin "+") (pinfunction "+_+") (pintype "passive"))
      (node (ref "C117") (pin "2") (pinfunction "2_2") (pintype "passive"))
      (node (ref "C17") (pin "+") (pinfunction "+_+") (pintype "passive"))
      (node (ref "C24") (pin "1") (pinfunction "+_1") (pintype "passive"))
      (node (ref "C27") (pin "2") (pinfunction "2_2") (pintype "passive"))
      (node (ref "C33") (pin "1") (pinfunction "1_1") (pintype "passive"))
      (node (ref "C34") (pin "1") (pinfunction "1_1") (pintype "passive"))
      (node (ref "C40") (pin "+") (pinfunction "+_+") (pintype "passive"))
      (node (ref "C45") (pin "2") (pinfunction "2_2") (pintype "passive"))
      (node (ref "C47") (pin "2") (pinfunction "2_2") (pintype "passive"))
      (node (ref "C8") (pin "1") (pinfunction "1_1") (pintype "passive"))
      (node (ref "C9") (pin "1") (pinfunction "1_1") (pintype "passive"))
      (node (ref "IC1") (pin "OUT") (pinfunction "OUT_OUT") (pintype "output"))
      (node (ref "Q1") (pin "2") (pinfunction "E_2") (pintype "passive"))
      (node (ref "R1") (pin "1") (pinfunction "1_1") (pintype "passive"))
      (node (ref "R62") (pin "2") (pinfunction "2_2") (pintype "passive"))
      (node (ref "R66") (pin "1") (pinfunction "1_1") (pintype "passive"))
      (node (ref "SJ2") (pin "3") (pinfunction "3_3") (pintype "passive"))
      (node (ref "SJ3") (pin "3") (pinfunction "3_3") (pintype "passive"))
      (node (ref "SJ4") (pin "3") (pinfunction "3_3") (pintype "passive"))
      (node (ref "SJ5") (pin "3") (pinfunction "3_3") (pintype "passive"))
      (node (ref "SJ6") (pin "3") (pinfunction "3_3") (pintype "passive"))
      (node (ref "U$1") (pin "018") (pinfunction "IOVDD_018") (pintype "bidirectional"))
      (node (ref "U$1") (pin "038") (pinfunction "IOVDD2_038") (pintype "bidirectional"))
      (node (ref "U$1") (pin "056") (pinfunction "IOVDD3_056") (pintype "bidirectional"))
      (node (ref "U$1") (pin "2") (pinfunction "IOVDD4_2") (pintype "bidirectional"))
      (node (ref "U$15") (pin "10") (pinfunction "VI/O_10") (pintype "bidirectional"))
      (node (ref "U$15") (pin "19") (pinfunction "GPO1_19") (pintype "bidirectional"))
      (node (ref "U$17") (pin "17") (pinfunction "DVDD_17") (pintype "bidirectional"))
      (node (ref "U$17") (pin "32") (pinfunction "DVDD_32") (pintype "bidirectional"))
      (node (ref "U$40") (pin "10") (pinfunction "VCCC_10") (pintype "bidirectional"))
      (node (ref "U$40") (pin "14") (pinfunction "VCOM_14") (pintype "bidirectional"))
      (node (ref "U$40") (pin "17") (pinfunction "VCCP1_17") (pintype "bidirectional"))
      (node (ref "U$40") (pin "19") (pinfunction "VCCP2_19") (pintype "bidirectional"))
      (node (ref "U$40") (pin "23") (pinfunction "VCCX_23") (pintype "bidirectional"))
      (node (ref "U$40") (pin "27") (pinfunction "VDD_27") (pintype "bidirectional"))
      (node (ref "U$40") (pin "3") (pinfunction "VBUS_3") (pintype "bidirectional"))
      (node (ref "U$40") (pin "8") (pinfunction "SEL0_8") (pintype "bidirectional"))
      (node (ref "U$43") (pin "1") (pinfunction "A_1") (pintype "bidirectional"))
      (node (ref "U$43") (pin "5") (pinfunction "VCC_5") (pintype "bidirectional"))
      (node (ref "U$52") (pin "3") (pinfunction "VCC_3") (pintype "bidirectional"))
      (node (ref "U$8") (pin "1") (pinfunction "VCC_1") (pintype "bidirectional"))
    )
    (net (code "7") (name "5V") (class "Default")
      (node (ref "C23") (pin "1") (pinfunction "+_1") (pintype "passive"))
      (node (ref "IC1") (pin "IN") (pinfunction "IN_IN") (pintype "input"))
      (node (ref "IC3") (pin "IN") (pinfunction "IN_IN") (pintype "input"))
      (node (ref "JP6") (pin "3") (pinfunction "3_3") (pintype "passive"))
      (node (ref "U$14") (pin "1") (pinfunction "IN_1") (pintype "input"))
    )
    (net (code "8") (name "BCLK0") (class "Default")
      (node (ref "R6") (pin "1") (pinfunction "1_1") (pintype "passive"))
      (node (ref "U$1") (pin "057") (pinfunction "BCLK0_057") (pintype "bidirectional"))
      (node (ref "U$13") (pin "24") (pinfunction "PCM_CLK_24") (pintype "bidirectional"))
    )
    (net (code "9") (name "BCLK1") (class "Default")
      (node (ref "U$1") (pin "060") (pinfunction "BCLK1_060") (pintype "bidirectional"))
      (node (ref "U$15") (pin "17") (pinfunction "GPO3/DCLK_17") (pintype "bidirectional"))
    )
    (net (code "10") (name "BCLK2") (class "Default")
      (node (ref "U$1") (pin "065") (pinfunction "BCLK2_065") (pintype "bidirectional"))
      (node (ref "U$17") (pin "28") (pinfunction "BCLKOUT_28") (pintype "bidirectional"))
    )
    (net (code "11") (name "BCLK3") (class "Default")
      (node (ref "JP14") (pin "1") (pinfunction "1_1") (pintype "passive"))
      (node (ref "U$1") (pin "068") (pinfunction "BCLK3_068") (pintype "bidirectional"))
    )
    (net (code "12") (name "BCLK_OUT0") (class "Default")
      (node (ref "R6") (pin "2") (pinfunction "2_2") (pintype "passive"))
      (node (ref "U$1") (pin "040") (pinfunction "BCLK0_OUT_040") (pintype "bidirectional"))
    )
    (net (code "13") (name "BCLK_OUT1") (class "Default")
      (node (ref "U$1") (pin "043") (pinfunction "BCLK1_OUT_043") (pintype "bidirectional"))
      (node (ref "U$17") (pin "21") (pinfunction "BCLKIN_21") (pintype "bidirectional"))
    )
    (net (code "14") (name "BCLK_OUT2") (class "Default")
      (node (ref "U$1") (pin "048") (pinfunction "BCLK2_OUT_048") (pintype "bidirectional"))
    )
    (net (code "15") (name "BCLK_OUT3") (class "Default")
      (node (ref "U$1") (pin "051") (pinfunction "BCLK3_OUT_051") (pintype "bidirectional"))
    )
    (net (code "16") (name "BT_CTS") (class "Default")
      (node (ref "JP3") (pin "4") (pinfunction "4_4") (pintype "passive"))
      (node (ref "U$13") (pin "14") (pinfunction "UART_CTS_14") (pintype "bidirectional"))
    )
    (net (code "17") (name "BT_RTS") (class "Default")
      (node (ref "JP3") (pin "5") (pinfunction "5_5") (pintype "passive"))
      (node (ref "U$13") (pin "13") (pinfunction "UART_RTS_13") (pintype "bidirectional"))
    )
    (net (code "18") (name "BT_RXI") (class "Default")
      (node (ref "JP3") (pin "2") (pinfunction "2_2") (pintype "passive"))
      (node (ref "U$13") (pin "16") (pinfunction "UART_RX_16") (pintype "bidirectional"))
    )
    (net (code "19") (name "BT_TXO") (class "Default")
      (node (ref "JP3") (pin "3") (pinfunction "3_3") (pintype "passive"))
      (node (ref "U$13") (pin "15") (pinfunction "UART_TX_15") (pintype "bidirectional"))
    )
    (net (code "20") (name "CLOCK") (class "Default")
      (node (ref "U$1") (pin "023") (pinfunction "CLKOUT_023") (pintype "bidirectional"))
      (node (ref "U$17") (pin "2") (pinfunction "MCLK-IN_2") (pintype "bidirectional"))
    )
    (net (code "21") (name "DAC3L0") (class "Default")
      (node (ref "R18") (pin "1") (pinfunction "1_1") (pintype "passive"))
      (node (ref "U$17") (pin "6") (pinfunction "DAC3_L+_6") (pintype "bidirectional"))
    )
    (net (code "22") (name "DAC3L1") (class "Default")
      (node (ref "R19") (pin "1") (pinfunction "1_1") (pintype "passive"))
      (node (ref "U$17") (pin "7") (pinfunction "DAC3_L-_7") (pintype "bidirectional"))
    )
    (net (code "23") (name "DAC3R0") (class "Default")
      (node (ref "R20") (pin "1") (pinfunction "1_1") (pintype "passive"))
      (node (ref "U$17") (pin "8") (pinfunction "DAC3_R+_8") (pintype "bidirectional"))
    )
    (net (code "24") (name "DAC3R1") (class "Default")
      (node (ref "R21") (pin "1") (pinfunction "1_1") (pintype "passive"))
      (node (ref "U$17") (pin "9") (pinfunction "DAC3_R-_9") (pintype "bidirectional"))
    )
    (net (code "25") (name "DAC4L0") (class "Default")
      (node (ref "R4") (pin "1") (pinfunction "1_1") (pintype "passive"))
      (node (ref "U$17") (pin "10") (pinfunction "DAC4_L+_10") (pintype "bidirectional"))
    )
    (net (code "26") (name "DAC4L1") (class "Default")
      (node (ref "R7") (pin "1") (pinfunction "1_1") (pintype "passive"))
      (node (ref "U$17") (pin "11") (pinfunction "DAC4_L-_11") (pintype "bidirectional"))
    )
    (net (code "27") (name "DAC4R0") (class "Default")
      (node (ref "R8") (pin "1") (pinfunction "1_1") (pintype "passive"))
      (node (ref "U$17") (pin "12") (pinfunction "DAC4_R+_12") (pintype "bidirectional"))
    )
    (net (code "28") (name "DAC4R1") (class "Default")
      (node (ref "R9") (pin "1") (pinfunction "1_1") (pintype "passive"))
      (node (ref "U$17") (pin "13") (pinfunction "DAC4_R-_13") (pintype "bidirectional"))
    )
    (net (code "29") (name "DATA0") (class "Default")
      (node (ref "U$1") (pin "059") (pinfunction "DATA0_059") (pintype "bidirectional"))
      (node (ref "U$13") (pin "22") (pinfunction "PCM_OUT_22") (pintype "bidirectional"))
    )
    (net (code "30") (name "DATA1") (class "Default")
      (node (ref "U$1") (pin "062") (pinfunction "DATA1_062") (pintype "bidirectional"))
      (node (ref "U$15") (pin "15") (pinfunction "DOUT_15") (pintype "bidirectional"))
    )
    (net (code "31") (name "DATA2") (class "Default")
      (node (ref "U$1") (pin "067") (pinfunction "DATA2_067") (pintype "bidirectional"))
      (node (ref "U$17") (pin "27") (pinfunction "DATAOUT0_27") (pintype "bidirectional"))
    )
    (net (code "32") (name "DATA3") (class "Default")
      (node (ref "JP14") (pin "3") (pinfunction "3_3") (pintype "passive"))
      (node (ref "U$1") (pin "070") (pinfunction "DATA3_070") (pintype "bidirectional"))
    )
    (net (code "33") (name "DATA_OUT0") (class "Default")
      (node (ref "U$1") (pin "041") (pinfunction "DATA0_OUT_041") (pintype "bidirectional"))
      (node (ref "U$13") (pin "21") (pinfunction "PCM_IN_21") (pintype "bidirectional"))
    )
    (net (code "34") (name "DATA_OUT1") (class "Default")
      (node (ref "U$1") (pin "044") (pinfunction "DATA1_OUT_044") (pintype "bidirectional"))
      (node (ref "U$17") (pin "20") (pinfunction "DATAIN0_20") (pintype "bidirectional"))
    )
    (net (code "35") (name "DATA_OUT2") (class "Default")
      (node (ref "U$1") (pin "049") (pinfunction "DATA2_OUT_049") (pintype "bidirectional"))
    )
    (net (code "36") (name "DATA_OUT3") (class "Default")
      (node (ref "U$1") (pin "052") (pinfunction "DATA3_OUT_052") (pintype "bidirectional"))
    )
    (net (code "37") (name "FILTER") (class "Default")
      (node (ref "C39") (pin "+") (pinfunction "+_+") (pintype "passive"))
      (node (ref "C41") (pin "1") (pinfunction "1_1") (pintype "passive"))
      (node (ref "U$17") (pin "47") (pinfunction "FILT_47") (pintype "bidirectional"))
    )
    (net (code "38") (name "GND") (class "Default")
      (node (ref "C1") (pin "2") (pinfunction "-_2") (pintype "passive"))
      (node (ref "C10") (pin "2") (pinfunction "2_2") (pintype "passive"))
      (node (ref "C100") (pin "2") (pinfunction "2_2") (pintype "passive"))
      (node (ref "C101") (pin "-") (pinfunction "-_-") (pintype "passive"))
      (node (ref "C102") (pin "-") (pinfunction "-_-") (pintype "passive"))
      (node (ref "C104") (pin "-") (pinfunction "-_-") (pintype "passive"))
      (node (ref "C107") (pin "-") (pinfunction "-_-") (pintype "passive"))
      (node (ref "C11") (pin "2") (pinfunction "2_2") (pintype "passive"))
      (node (ref "C110") (pin "-") (pinfunction "-_-") (pintype "passive"))
      (node (ref "C112") (pin "-") (pinfunction "-_-") (pintype "passive"))
      (node (ref "C113") (pin "1") (pinfunction "1_1") (pintype "passive"))
      (node (ref "C114") (pin "1") (pinfunction "1_1") (pintype "passive"))
      (node (ref "C117") (pin "1") (pinfunction "1_1") (pintype "passive"))
      (node (ref "C12") (pin "-") (pinfunction "-_-") (pintype "passive"))
      (node (ref "C13") (pin "2") (pinfunction "2_2") (pintype "passive"))
      (node (ref "C14") (pin "2") (pinfunction "2_2") (pintype "passive"))
      (node (ref "C15") (pin "2") (pinfunction "2_2") (pintype "passive"))
      (node (ref "C16") (pin "2") (pinfunction "2_2") (pintype "passive"))
      (node (ref "C17") (pin "-") (pinfunction "-_-") (pintype "passive"))
      (node (ref "C18") (pin "-") (pinfunction "-_-") (pintype "passive"))
      (node (ref "C19") (pin "2") (pinfunction "2_2") (pintype "passive"))
      (node (ref "C2") (pin "1") (pinfunction "+_1") (pintype "passive"))
      (node (ref "C20") (pin "1") (pinfunction "1_1") (pintype "passive"))
      (node (ref "C23") (pin "2") (pinfunction "-_2") (pintype "passive"))
      (node (ref "C24") (pin "2") (pinfunction "-_2") (pintype "passive"))
      (node (ref "C25") (pin "1") (pinfunction "1_1") (pintype "passive"))
      (node (ref "C26") (pin "1") (pinfunction "1_1") (pintype "passive"))
      (node (ref "C27") (pin "1") (pinfunction "1_1") (pintype "passive"))
      (node (ref "C28") (pin "-") (pinfunction "-_-") (pintype "passive"))
      (node (ref "C29") (pin "-") (pinfunction "-_-") (pintype "passive"))
      (node (ref "C3") (pin "2") (pinfunction "2_2") (pintype "passive"))
      (node (ref "C30") (pin "2") (pinfunction "2_2") (pintype "passive"))
      (node (ref "C32") (pin "-") (pinfunction "-_-") (pintype "passive"))
      (node (ref "C33") (pin "2") (pinfunction "2_2") (pintype "passive"))
      (node (ref "C34") (pin "2") (pinfunction "2_2") (pintype "passive"))
      (node (ref "C35") (pin "2") (pinfunction "2_2") (pintype "passive"))
      (node (ref "C36") (pin "2") (pinfunction "2_2") (pintype "passive"))
      (node (ref "C37") (pin "2") (pinfunction "2_2") (pintype "passive"))
      (node (ref "C38") (pin "2") (pinfunction "2_2") (pintype "passive"))
      (node (ref "C39") (pin "-") (pinfunction "-_-") (pintype "passive"))
      (node (ref "C4") (pin "2") (pinfunction "2_2") (pintype "passive"))
      (node (ref "C40") (pin "-") (pinfunction "-_-") (pintype "passive"))
      (node (ref "C41") (pin "2") (pinfunction "2_2") (pintype "passive"))
      (node (ref "C42") (pin "2") (pinfunction "-_2") (pintype "passive"))
      (node (ref "C43") (pin "-") (pinfunction "-_-") (pintype "passive"))
      (node (ref "C44") (pin "2") (pinfunction "2_2") (pintype "passive"))
      (node (ref "C45") (pin "1") (pinfunction "1_1") (pintype "passive"))
      (node (ref "C46") (pin "-") (pinfunction "-_-") (pintype "passive"))
      (node (ref "C47") (pin "1") (pinfunction "1_1") (pintype "passive"))
      (node (ref "C48") (pin "2") (pinfunction "2_2") (pintype "passive"))
      (node (ref "C49") (pin "2") (pinfunction "2_2") (pintype "passive"))
      (node (ref "C5") (pin "2") (pinfunction "2_2") (pintype "passive"))
      (node (ref "C50") (pin "2") (pinfunction "2_2") (pintype "passive"))
      (node (ref "C52") (pin "+") (pinfunction "+_+") (pintype "passive"))
      (node (ref "C53") (pin "-") (pinfunction "-_-") (pintype "passive"))
      (node (ref "C54") (pin "+") (pinfunction "+_+") (pintype "passive"))
      (node (ref "C55") (pin "2") (pinfunction "2_2") (pintype "passive"))
      (node (ref "C56") (pin "1") (pinfunction "1_1") (pintype "passive"))
      (node (ref "C59") (pin "2") (pinfunction "2_2") (pintype "passive"))
      (node (ref "C6") (pin "2") (pinfunction "2_2") (pintype "passive"))
      (node (ref "C60") (pin "1") (pinfunction "1_1") (pintype "passive"))
      (node (ref "C62") (pin "1") (pinfunction "1_1") (pintype "passive"))
      (node (ref "C64") (pin "1") (pinfunction "1_1") (pintype "passive"))
      (node (ref "C65") (pin "2") (pinfunction "2_2") (pintype "passive"))
      (node (ref "C66") (pin "2") (pinfunction "2_2") (pintype "passive"))
      (node (ref "C67") (pin "2") (pinfunction "2_2") (pintype "passive"))
      (node (ref "C68") (pin "2") (pinfunction "2_2") (pintype "passive"))
      (node (ref "C7") (pin "2") (pinfunction "2_2") (pintype "passive"))
      (node (ref "C70") (pin "2") (pinfunction "2_2") (pintype "passive"))
      (node (ref "C74") (pin "2") (pinfunction "2_2") (pintype "passive"))
      (node (ref "C75") (pin "1") (pinfunction "1_1") (pintype "passive"))
      (node (ref "C78") (pin "2") (pinfunction "2_2") (pintype "passive"))
      (node (ref "C79") (pin "1") (pinfunction "1_1") (pintype "passive"))
      (node (ref "C8") (pin "2") (pinfunction "2_2") (pintype "passive"))
      (node (ref "C80") (pin "2") (pinfunction "2_2") (pintype "passive"))
      (node (ref "C81") (pin "+") (pinfunction "+_+") (pintype "passive"))
      (node (ref "C82") (pin "+") (pinfunction "+_+") (pintype "passive"))
      (node (ref "C85") (pin "2") (pinfunction "2_2") (pintype "passive"))
      (node (ref "C86") (pin "1") (pinfunction "1_1") (pintype "passive"))
      (node (ref "C88") (pin "2") (pinfunction "2_2") (pintype "passive"))
      (node (ref "C89") (pin "1") (pinfunction "1_1") (pintype "passive"))
      (node (ref "C9") (pin "2") (pinfunction "2_2") (pintype "passive"))
      (node (ref "C90") (pin "2") (pinfunction "2_2") (pintype "passive"))
      (node (ref "C95") (pin "2") (pinfunction "2_2") (pintype "passive"))
      (node (ref "C96") (pin "1") (pinfunction "1_1") (pintype "passive"))
      (node (ref "C98") (pin "2") (pinfunction "2_2") (pintype "passive"))
      (node (ref "C99") (pin "1") (pinfunction "1_1") (pintype "passive"))
      (node (ref "IC1") (pin "GND") (pinfunction "GND_GND") (pintype "input"))
      (node (ref "IC3") (pin "GND") (pinfunction "GND_GND") (pintype "input"))
      (node (ref "IC5") (pin "3") (pinfunction "+IN_3") (pintype "input"))
      (node (ref "IC5") (pin "5") (pinfunction "+IN_5") (pintype "input"))
      (node (ref "IC6") (pin "3") (pinfunction "+IN_3") (pintype "input"))
      (node (ref "IC6") (pin "5") (pinfunction "+IN_5") (pintype "input"))
      (node (ref "IC7") (pin "3") (pinfunction "+IN_3") (pintype "input"))
      (node (ref "IC7") (pin "5") (pinfunction "+IN_5") (pintype "input"))
      (node (ref "JP1") (pin "2") (pinfunction "2_2") (pintype "passive"))
      (node (ref "JP10") (pin "2") (pinfunction "2_2") (pintype "passive"))
      (node (ref "JP11") (pin "2") (pinfunction "2_2") (pintype "passive"))
      (node (ref "JP12") (pin "2") (pinfunction "2_2") (pintype "passive"))
      (node (ref "JP13") (pin "1") (pinfunction "1_1") (pintype "passive"))
      (node (ref "JP14") (pin "4") (pinfunction "4_4") (pintype "passive"))
      (node (ref "JP15") (pin "1") (pinfunction "1_1") (pintype "passive"))
      (node (ref "JP3") (pin "1") (pinfunction "1_1") (pintype "passive"))
      (node (ref "JP3") (pin "6") (pinfunction "6_6") (pintype "passive"))
      (node (ref "JP4") (pin "1") (pinfunction "1_1") (pintype "passive"))
      (node (ref "JP5") (pin "2") (pinfunction "2_2") (pintype "passive"))
      (node (ref "JP6") (pin "1") (pinfunction "1_1") (pintype "passive"))
      (node (ref "JP7") (pin "2") (pinfunction "2_2") (pintype "passive"))
      (node (ref "JP8") (pin "2") (pinfunction "2_2") (pintype "passive"))
      (node (ref "JP9") (pin "2") (pinfunction "2_2") (pintype "passive"))
      (node (ref "LED1") (pin "C") (pinfunction "C_C") (pintype "passive"))
      (node (ref "LED2") (pin "C") (pinfunction "C_C") (pintype "passive"))
      (node (ref "LED3") (pin "C") (pinfunction "C_C") (pintype "passive"))
      (node (ref "LED4") (pin "C") (pinfunction "C_C") (pintype "passive"))
      (node (ref "R10") (pin "2") (pinfunction "2_2") (pintype "passive"))
      (node (ref "R11") (pin "2") (pinfunction "2_2") (pintype "passive"))
      (node (ref "R14") (pin "2") (pinfunction "2_2") (pintype "passive"))
      (node (ref "R15") (pin "2") (pinfunction "2_2") (pintype "passive"))
      (node (ref "R56") (pin "2") (pinfunction "2_2") (pintype "passive"))
      (node (ref "R57") (pin "1") (pinfunction "1_1") (pintype "passive"))
      (node (ref "S1") (pin "3") (pinfunction "3_3") (pintype "passive"))
      (node (ref "S1") (pin "4") (pinfunction "4_4") (pintype "passive"))
      (node (ref "SJ2") (pin "1") (pinfunction "1_1") (pintype "passive"))
      (node (ref "SJ3") (pin "1") (pinfunction "1_1") (pintype "passive"))
      (node (ref "SJ4") (pin "1") (pinfunction "1_1") (pintype "passive"))
      (node (ref "SJ5") (pin "1") (pinfunction "1_1") (pintype "passive"))
      (node (ref "SJ6") (pin "1") (pinfunction "1_1") (pintype "passive"))
      (node (ref "U$1") (pin "017") (pinfunction "DGND2_017") (pintype "bidirectional"))
      (node (ref "U$1") (pin "019") (pinfunction "DGND3_019") (pintype "bidirectional"))
      (node (ref "U$1") (pin "025") (pinfunction "DGND4_025") (pintype "bidirectional"))
      (node (ref "U$1") (pin "036") (pinfunction "DGND5_036") (pintype "bidirectional"))
      (node (ref "U$1") (pin "037") (pinfunction "DGND6_037") (pintype "bidirectional"))
      (node (ref "U$1") (pin "054") (pinfunction "DGND7_054") (pintype "bidirectional"))
      (node (ref "U$1") (pin "055") (pinfunction "DGND8_055") (pintype "bidirectional"))
      (node (ref "U$1") (pin "072") (pinfunction "DGND9_072") (pintype "bidirectional"))
      (node (ref "U$1") (pin "1") (pinfunction "DGND_1") (pintype "bidirectional"))
      (node (ref "U$1") (pin "14") (pinfunction "PGND_14") (pintype "bidirectional"))
      (node (ref "U$1") (pin "6") (pinfunction "AGND_6") (pintype "bidirectional"))
      (node (ref "U$1") (pin "EXP") (pinfunction "PAD_EXP") (pintype "bidirectional"))
      (node (ref "U$13") (pin "36") (pinfunction "AGND_36") (pintype "bidirectional"))
      (node (ref "U$13") (pin "G1") (pinfunction "GND9_G1") (pintype "bidirectional"))
      (node (ref "U$13") (pin "G2") (pinfunction "GND8_G2") (pintype "bidirectional"))
      (node (ref "U$13") (pin "G3") (pinfunction "GND7_G3") (pintype "bidirectional"))
      (node (ref "U$13") (pin "G4") (pinfunction "GND6_G4") (pintype "bidirectional"))
      (node (ref "U$13") (pin "RFG1") (pinfunction "GND_RFG1") (pintype "bidirectional"))
      (node (ref "U$13") (pin "RFG2") (pinfunction "GND1_RFG2") (pintype "bidirectional"))
      (node (ref "U$13") (pin "RFG3") (pinfunction "GND2_RFG3") (pintype "bidirectional"))
      (node (ref "U$13") (pin "RFG4") (pinfunction "GND3_RFG4") (pintype "bidirectional"))
      (node (ref "U$13") (pin "RFG5") (pinfunction "GND4_RFG5") (pintype "bidirectional"))
      (node (ref "U$13") (pin "RFG6") (pinfunction "GND5_RFG6") (pintype "bidirectional"))
      (node (ref "U$14") (pin "2") (pinfunction "GND_2") (pintype "input"))
      (node (ref "U$15") (pin "12") (pinfunction "GND_12") (pintype "bidirectional"))
      (node (ref "U$15") (pin "18") (pinfunction "GPO2/INT_18") (pintype "bidirectional"))
      (node (ref "U$15") (pin "21") (pinfunction "GNDPAD_21") (pintype "bidirectional"))
      (node (ref "U$15") (pin "3") (pinfunction "RFGND_3") (pintype "bidirectional"))
      (node (ref "U$17") (pin "1") (pinfunction "AGND_1") (pintype "bidirectional"))
      (node (ref "U$17") (pin "16") (pinfunction "DGND_16") (pintype "bidirectional"))
      (node (ref "U$17") (pin "23") (pinfunction "VSUPP_23") (pintype "bidirectional"))
      (node (ref "U$17") (pin "24") (pinfunction "VSENSE_24") (pintype "bidirectional"))
      (node (ref "U$17") (pin "25") (pinfunction "VDRIVE_25") (pintype "bidirectional"))
      (node (ref "U$17") (pin "33") (pinfunction "DGND_33") (pintype "bidirectional"))
      (node (ref "U$17") (pin "4") (pinfunction "AGND_4") (pintype "bidirectional"))
      (node (ref "U$17") (pin "44") (pinfunction "AGND_44") (pintype "bidirectional"))
      (node (ref "U$17") (pin "46") (pinfunction "AGND_46") (pintype "bidirectional"))
      (node (ref "U$17") (pin "48") (pinfunction "AGND_48") (pintype "bidirectional"))
      (node (ref "U$35") (pin "7") (pinfunction "E_7") (pintype "bidirectional"))
      (node (ref "U$38") (pin "7") (pinfunction "E_7") (pintype "bidirectional"))
      (node (ref "U$39") (pin "7") (pinfunction "E_7") (pintype "bidirectional"))
      (node (ref "U$40") (pin "11") (pinfunction "AGNDC_11") (pintype "bidirectional"))
      (node (ref "U$40") (pin "18") (pinfunction "AGNDP_18") (pintype "bidirectional"))
      (node (ref "U$40") (pin "22") (pinfunction "AGNDX_22") (pintype "bidirectional"))
      (node (ref "U$40") (pin "26") (pinfunction "DGND_26") (pintype "bidirectional"))
      (node (ref "U$40") (pin "4") (pinfunction "DGNDU_4") (pintype "bidirectional"))
      (node (ref "U$43") (pin "3") (pinfunction "GND_3") (pintype "bidirectional"))
      (node (ref "U$52") (pin "1") (pinfunction "GND_1") (pintype "bidirectional"))
      (node (ref "U$8") (pin "5") (pinfunction "GND_5") (pintype "bidirectional"))
    )
    (net (code "39") (name "LRCLK0") (class "Default")
      (node (ref "R5") (pin "1") (pinfunction "1_1") (pintype "passive"))
      (node (ref "U$1") (pin "058") (pinfunction "LRCLK0_058") (pintype "bidirectional"))
      (node (ref "U$13") (pin "23") (pinfunction "PCM_SYNC_23") (pintype "bidirectional"))
    )
    (net (code "40") (name "LRCLK1") (class "Default")
      (node (ref "U$1") (pin "061") (pinfunction "LRCLK1_061") (pintype "bidirectional"))
      (node (ref "U$15") (pin "16") (pinfunction "DFS_16") (pintype "bidirectional"))
    )
    (net (code "41") (name "LRCLK2") (class "Default")
      (node (ref "U$1") (pin "066") (pinfunction "LRCLK2_066") (pintype "bidirectional"))
      (node (ref "U$17") (pin "29") (pinfunction "LRLCKOUT_29") (pintype "bidirectional"))
    )
    (net (code "42") (name "LRCLK3") (class "Default")
      (node (ref "JP14") (pin "2") (pinfunction "2_2") (pintype "passive"))
      (node (ref "U$1") (pin "069") (pinfunction "LRCLK3_069") (pintype "bidirectional"))
    )
    (net (code "43") (name "LRCLK_OUT0") (class "Default")
      (node (ref "R5") (pin "2") (pinfunction "2_2") (pintype "passive"))
      (node (ref "U$1") (pin "039") (pinfunction "LRCLK0_OUT_039") (pintype "bidirectional"))
    )
    (net (code "44") (name "LRCLK_OUT1") (class "Default")
      (node (ref "U$1") (pin "042") (pinfunction "LRCLK1_OUT_042") (pintype "bidirectional"))
      (node (ref "U$17") (pin "22") (pinfunction "LRCLKIN_22") (pintype "bidirectional"))
    )
    (net (code "45") (name "LRCLK_OUT2") (class "Default")
      (node (ref "U$1") (pin "047") (pinfunction "LRCLK2_OUT_047") (pintype "bidirectional"))
    )
    (net (code "46") (name "LRCLK_OUT3") (class "Default")
      (node (ref "U$1") (pin "050") (pinfunction "LRCLK3_OUT_050") (pintype "bidirectional"))
    )
    (net (code "47") (name "Net-(C22-Pad2)") (class "Default")
      (node (ref "C22") (pin "2") (pinfunction "2_2") (pintype "passive"))
      (node (ref "R2") (pin "2") (pinfunction "2_2") (pintype "passive"))
    )
    (net (code "48") (name "Net-(C25-Pad2)") (class "Default")
      (node (ref "C25") (pin "2") (pinfunction "2_2") (pintype "passive"))
      (node (ref "R3") (pin "1") (pinfunction "1_1") (pintype "passive"))
      (node (ref "Y1") (pin "1") (pinfunction "1_1") (pintype "passive"))
    )
    (net (code "49") (name "Net-(C31-Pad1)") (class "Default")
      (node (ref "C31") (pin "1") (pinfunction "1_1") (pintype "passive"))
      (node (ref "JP4") (pin "2") (pinfunction "2_2") (pintype "passive"))
    )
    (net (code "50") (name "Net-(C57-Pad+)") (class "Default")
      (node (ref "C57") (pin "+") (pinfunction "+_+") (pintype "passive"))
      (node (ref "R36") (pin "2") (pinfunction "2_2") (pintype "passive"))
    )
    (net (code "51") (name "Net-(C58-Pad+)") (class "Default")
      (node (ref "C58") (pin "+") (pinfunction "+_+") (pintype "passive"))
      (node (ref "R37") (pin "2") (pinfunction "2_2") (pintype "passive"))
    )
    (net (code "52") (name "Net-(C72-Pad-)") (class "Default")
      (node (ref "C72") (pin "-") (pinfunction "-_-") (pintype "passive"))
      (node (ref "R34") (pin "2") (pinfunction "2_2") (pintype "passive"))
    )
    (net (code "53") (name "Net-(C73-Pad-)") (class "Default")
      (node (ref "C73") (pin "-") (pinfunction "-_-") (pintype "passive"))
      (node (ref "R35") (pin "2") (pinfunction "2_2") (pintype "passive"))
    )
    (net (code "54") (name "Net-(C83-Pad+)") (class "Default")
      (node (ref "C83") (pin "+") (pinfunction "+_+") (pintype "passive"))
      (node (ref "R42") (pin "2") (pinfunction "2_2") (pintype "passive"))
    )
    (net (code "55") (name "Net-(C84-Pad+)") (class "Default")
      (node (ref "C84") (pin "+") (pinfunction "+_+") (pintype "passive"))
      (node (ref "R43") (pin "2") (pinfunction "2_2") (pintype "passive"))
    )
    (net (code "56") (name "Net-(C93-Pad+)") (class "Default")
      (node (ref "C93") (pin "+") (pinfunction "+_+") (pintype "passive"))
      (node (ref "R48") (pin "2") (pinfunction "2_2") (pintype "passive"))
    )
    (net (code "57") (name "Net-(C94-Pad+)") (class "Default")
      (node (ref "C94") (pin "+") (pinfunction "+_+") (pintype "passive"))
      (node (ref "R49") (pin "2") (pinfunction "2_2") (pintype "passive"))
    )
    (net (code "58") (name "Net-(C103-Pad+)") (class "Default")
      (node (ref "C103") (pin "+") (pinfunction "+_+") (pintype "passive"))
      (node (ref "C88") (pin "1") (pinfunction "1_1") (pintype "passive"))
      (node (ref "R46") (pin "1") (pinfunction "1_1") (pintype "passive"))
    )
    (net (code "59") (name "Net-(C103-Pad-)") (class "Default")
      (node (ref "C103") (pin "-") (pinfunction "-_-") (pintype "passive"))
      (node (ref "JP12") (pin "1") (pinfunction "1_1") (pintype "passive"))
    )
    (net (code "60") (name "Net-(C105-Pad+)") (class "Default")
      (node (ref "C105") (pin "+") (pinfunction "+_+") (pintype "passive"))
      (node (ref "C98") (pin "1") (pinfunction "1_1") (pintype "passive"))
      (node (ref "R52") (pin "1") (pinfunction "1_1") (pintype "passive"))
    )
    (net (code "61") (name "Net-(C105-Pad-)") (class "Default")
      (node (ref "C105") (pin "-") (pinfunction "-_-") (pintype "passive"))
      (node (ref "JP12") (pin "3") (pinfunction "3_3") (pintype "passive"))
    )
    (net (code "62") (name "Net-(C106-Pad+)") (class "Default")
      (node (ref "C106") (pin "+") (pinfunction "+_+") (pintype "passive"))
      (node (ref "C78") (pin "1") (pinfunction "1_1") (pintype "passive"))
      (node (ref "R40") (pin "1") (pinfunction "1_1") (pintype "passive"))
    )
    (net (code "63") (name "Net-(C106-Pad-)") (class "Default")
      (node (ref "C106") (pin "-") (pinfunction "-_-") (pintype "passive"))
      (node (ref "JP11") (pin "1") (pinfunction "1_1") (pintype "passive"))
    )
    (net (code "64") (name "Net-(IC2A-+IN)") (class "Default")
      (node (ref "IC2") (pin "3") (pinfunction "+IN_3") (pintype "input"))
      (node (ref "R13") (pin "1") (pinfunction "1_1") (pintype "passive"))
      (node (ref "R4") (pin "2") (pinfunction "2_2") (pintype "passive"))
    )
    (net (code "65") (name "Net-(IC2A--IN)") (class "Default")
      (node (ref "IC2") (pin "2") (pinfunction "-IN_2") (pintype "input"))
      (node (ref "R10") (pin "1") (pinfunction "1_1") (pintype "passive"))
      (node (ref "R7") (pin "2") (pinfunction "2_2") (pintype "passive"))
    )
    (net (code "66") (name "Net-(IC2A-OUT)") (class "Default")
      (node (ref "IC2") (pin "1") (pinfunction "OUT_1") (pintype "output"))
      (node (ref "JP5") (pin "1") (pinfunction "1_1") (pintype "passive"))
      (node (ref "R13") (pin "2") (pinfunction "2_2") (pintype "passive"))
    )
    (net (code "67") (name "Net-(IC2B-+IN)") (class "Default")
      (node (ref "IC2") (pin "5") (pinfunction "+IN_5") (pintype "input"))
      (node (ref "R12") (pin "1") (pinfunction "1_1") (pintype "passive"))
      (node (ref "R8") (pin "2") (pinfunction "2_2") (pintype "passive"))
    )
    (net (code "68") (name "Net-(IC2B--IN)") (class "Default")
      (node (ref "IC2") (pin "6") (pinfunction "-IN_6") (pintype "input"))
      (node (ref "R11") (pin "1") (pinfunction "1_1") (pintype "passive"))
      (node (ref "R9") (pin "2") (pinfunction "2_2") (pintype "passive"))
    )
    (net (code "69") (name "Net-(IC2B-OUT)") (class "Default")
      (node (ref "IC2") (pin "7") (pinfunction "OUT_7") (pintype "output"))
      (node (ref "JP5") (pin "3") (pinfunction "3_3") (pintype "passive"))
      (node (ref "R12") (pin "2") (pinfunction "2_2") (pintype "passive"))
    )
    (net (code "70") (name "Net-(IC4A-+IN)") (class "Default")
      (node (ref "IC4") (pin "3") (pinfunction "+IN_3") (pintype "input"))
      (node (ref "R17") (pin "1") (pinfunction "1_1") (pintype "passive"))
      (node (ref "R18") (pin "2") (pinfunction "2_2") (pintype "passive"))
    )
    (net (code "71") (name "Net-(IC4A--IN)") (class "Default")
      (node (ref "IC4") (pin "2") (pinfunction "-IN_2") (pintype "input"))
      (node (ref "R14") (pin "1") (pinfunction "1_1") (pintype "passive"))
      (node (ref "R19") (pin "2") (pinfunction "2_2") (pintype "passive"))
    )
    (net (code "72") (name "Net-(IC4A-OUT)") (class "Default")
      (node (ref "IC4") (pin "1") (pinfunction "OUT_1") (pintype "output"))
      (node (ref "JP7") (pin "1") (pinfunction "1_1") (pintype "passive"))
      (node (ref "R17") (pin "2") (pinfunction "2_2") (pintype "passive"))
    )
    (net (code "73") (name "Net-(IC4B-+IN)") (class "Default")
      (node (ref "IC4") (pin "5") (pinfunction "+IN_5") (pintype "input"))
      (node (ref "R16") (pin "1") (pinfunction "1_1") (pintype "passive"))
      (node (ref "R20") (pin "2") (pinfunction "2_2") (pintype "passive"))
    )
    (net (code "74") (name "Net-(IC4B--IN)") (class "Default")
      (node (ref "IC4") (pin "6") (pinfunction "-IN_6") (pintype "input"))
      (node (ref "R15") (pin "1") (pinfunction "1_1") (pintype "passive"))
      (node (ref "R21") (pin "2") (pinfunction "2_2") (pintype "passive"))
    )
    (net (code "75") (name "Net-(IC4B-OUT)") (class "Default")
      (node (ref "IC4") (pin "7") (pinfunction "OUT_7") (pintype "output"))
      (node (ref "JP7") (pin "3") (pinfunction "3_3") (pintype "passive"))
      (node (ref "R16") (pin "2") (pinfunction "2_2") (pintype "passive"))
    )
    (net (code "76") (name "Net-(IC5A--IN)") (class "Default")
      (node (ref "IC5") (pin "2") (pinfunction "-IN_2") (pintype "input"))
      (node (ref "R38") (pin "1") (pinfunction "1_1") (pintype "passive"))
      (node (ref "R39") (pin "1") (pinfunction "1_1") (pintype "passive"))
    )
    (net (code "77") (name "Net-(IC5A-OUT)") (class "Default")
      (node (ref "C58") (pin "-") (pinfunction "-_-") (pintype "passive"))
      (node (ref "IC5") (pin "1") (pinfunction "OUT_1") (pintype "output"))
      (node (ref "R38") (pin "2") (pinfunction "2_2") (pintype "passive"))
    )
    (net (code "78") (name "Net-(IC5B--IN)") (class "Default")
      (node (ref "IC5") (pin "6") (pinfunction "-IN_6") (pintype "input"))
      (node (ref "R40") (pin "2") (pinfunction "2_2") (pintype "passive"))
      (node (ref "R41") (pin "1") (pinfunction "1_1") (pintype "passive"))
    )
    (net (code "79") (name "Net-(IC5B-OUT)") (class "Default")
      (node (ref "C57") (pin "-") (pinfunction "-_-") (pintype "passive"))
      (node (ref "IC5") (pin "7") (pinfunction "OUT_7") (pintype "output"))
      (node (ref "R39") (pin "2") (pinfunction "2_2") (pintype "passive"))
      (node (ref "R41") (pin "2") (pinfunction "2_2") (pintype "passive"))
    )
    (net (code "80") (name "Net-(IC6A--IN)") (class "Default")
      (node (ref "IC6") (pin "2") (pinfunction "-IN_2") (pintype "input"))
      (node (ref "R44") (pin "1") (pinfunction "1_1") (pintype "passive"))
      (node (ref "R45") (pin "1") (pinfunction "1_1") (pintype "passive"))
    )
    (net (code "81") (name "Net-(IC6A-OUT)") (class "Default")
      (node (ref "C84") (pin "-") (pinfunction "-_-") (pintype "passive"))
      (node (ref "IC6") (pin "1") (pinfunction "OUT_1") (pintype "output"))
      (node (ref "R44") (pin "2") (pinfunction "2_2") (pintype "passive"))
    )
    (net (code "82") (name "Net-(IC6B--IN)") (class "Default")
      (node (ref "IC6") (pin "6") (pinfunction "-IN_6") (pintype "input"))
      (node (ref "R46") (pin "2") (pinfunction "2_2") (pintype "passive"))
      (node (ref "R47") (pin "1") (pinfunction "1_1") (pintype "passive"))
    )
    (net (code "83") (name "Net-(IC6B-OUT)") (class "Default")
      (node (ref "C83") (pin "-") (pinfunction "-_-") (pintype "passive"))
      (node (ref "IC6") (pin "7") (pinfunction "OUT_7") (pintype "output"))
      (node (ref "R45") (pin "2") (pinfunction "2_2") (pintype "passive"))
      (node (ref "R47") (pin "2") (pinfunction "2_2") (pintype "passive"))
    )
    (net (code "84") (name "Net-(IC7A--IN)") (class "Default")
      (node (ref "IC7") (pin "2") (pinfunction "-IN_2") (pintype "input"))
      (node (ref "R50") (pin "1") (pinfunction "1_1") (pintype "passive"))
      (node (ref "R51") (pin "1") (pinfunction "1_1") (pintype "passive"))
    )
    (net (code "85") (name "Net-(IC7A-OUT)") (class "Default")
      (node (ref "C94") (pin "-") (pinfunction "-_-") (pintype "passive"))
      (node (ref "IC7") (pin "1") (pinfunction "OUT_1") (pintype "output"))
      (node (ref "R50") (pin "2") (pinfunction "2_2") (pintype "passive"))
    )
    (net (code "86") (name "Net-(IC7B--IN)") (class "Default")
      (node (ref "IC7") (pin "6") (pinfunction "-IN_6") (pintype "input"))
      (node (ref "R52") (pin "2") (pinfunction "2_2") (pintype "passive"))
      (node (ref "R53") (pin "1") (pinfunction "1_1") (pintype "passive"))
    )
    (net (code "87") (name "Net-(IC7B-OUT)") (class "Default")
      (node (ref "C93") (pin "-") (pinfunction "-_-") (pintype "passive"))
      (node (ref "IC7") (pin "7") (pinfunction "OUT_7") (pintype "output"))
      (node (ref "R51") (pin "2") (pinfunction "2_2") (pintype "passive"))
      (node (ref "R53") (pin "2") (pinfunction "2_2") (pintype "passive"))
    )
    (net (code "88") (name "Net-(JP10-Pad1)") (class "Default")
      (node (ref "JP10") (pin "1") (pinfunction "1_1") (pintype "passive"))
      (node (ref "R31") (pin "1") (pinfunction "1_1") (pintype "passive"))
    )
    (net (code "89") (name "Net-(JP10-Pad3)") (class "Default")
      (node (ref "JP10") (pin "3") (pinfunction "3_3") (pintype "passive"))
      (node (ref "R30") (pin "1") (pinfunction "1_1") (pintype "passive"))
    )
    (net (code "90") (name "Net-(JP13-Pad2)") (class "Default")
      (node (ref "JP13") (pin "2") (pinfunction "2_2") (pintype "passive"))
      (node (ref "R58") (pin "1") (pinfunction "1_1") (pintype "passive"))
      (node (ref "R60") (pin "1") (pinfunction "1_1") (pintype "passive"))
    )
    (net (code "91") (name "Net-(JP13-Pad3)") (class "Default")
      (node (ref "JP13") (pin "3") (pinfunction "3_3") (pintype "passive"))
      (node (ref "R59") (pin "1") (pinfunction "1_1") (pintype "passive"))
    )
    (net (code "92") (name "Net-(LED1-PadA)") (class "Default")
      (node (ref "LED1") (pin "A") (pinfunction "A_A") (pintype "passive"))
      (node (ref "R66") (pin "2") (pinfunction "2_2") (pintype "passive"))
    )
    (net (code "93") (name "Net-(LED2-PadA)") (class "Default")
      (node (ref "LED2") (pin "A") (pinfunction "A_A") (pintype "passive"))
      (node (ref "R65") (pin "2") (pinfunction "2_2") (pintype "passive"))
    )
    (net (code "94") (name "Net-(LED3-PadA)") (class "Default")
      (node (ref "LED3") (pin "A") (pinfunction "A_A") (pintype "passive"))
      (node (ref "R63") (pin "2") (pinfunction "2_2") (pintype "passive"))
    )
    (net (code "95") (name "Net-(LED4-PadA)") (class "Default")
      (node (ref "LED4") (pin "A") (pinfunction "A_A") (pintype "passive"))
      (node (ref "R64") (pin "2") (pinfunction "2_2") (pintype "passive"))
    )
    (net (code "96") (name "Net-(Q1-C)") (class "Default")
      (node (ref "C12") (pin "+") (pinfunction "+_+") (pintype "passive"))
      (node (ref "Q1") (pin "3") (pinfunction "C_3") (pintype "passive"))
      (node (ref "SJ1") (pin "1") (pinfunction "1_1") (pintype "passive"))
    )
    (net (code "97") (name "Net-(R55-Pad1)") (class "Default")
      (node (ref "R55") (pin "1") (pinfunction "1_1") (pintype "passive"))
      (node (ref "R56") (pin "1") (pinfunction "1_1") (pintype "passive"))
    )
    (net (code "98") (name "Net-(TP2-1)") (class "Default")
      (node (ref "TP2") (pin "P$1") (pinfunction "1_P$1") (pintype "bidirectional"))
      (node (ref "U$15") (pin "14") (pinfunction "LOUT_14") (pintype "bidirectional"))
    )
    (net (code "99") (name "Net-(TP3-1)") (class "Default")
      (node (ref "TP3") (pin "P$1") (pinfunction "1_P$1") (pintype "bidirectional"))
      (node (ref "U$15") (pin "13") (pinfunction "ROUT_13") (pintype "bidirectional"))
    )
    (net (code "100") (name "Net-(TP4-1)") (class "Default")
      (node (ref "TP4") (pin "P$1") (pinfunction "1_P$1") (pintype "bidirectional"))
      (node (ref "U$40") (pin "16") (pinfunction "VOUTL_16") (pintype "bidirectional"))
    )
    (net (code "101") (name "Net-(TP5-1)") (class "Default")
      (node (ref "TP5") (pin "P$1") (pinfunction "1_P$1") (pintype "bidirectional"))
      (node (ref "U$40") (pin "15") (pinfunction "VOUTR_15") (pintype "bidirectional"))
    )
    (net (code "102") (name "Net-(TP6-1)") (class "Default")
      (node (ref "TP6") (pin "P$1") (pinfunction "1_P$1") (pintype "bidirectional"))
      (node (ref "U$40") (pin "12") (pinfunction "VINL_12") (pintype "bidirectional"))
    )
    (net (code "103") (name "Net-(TP7-1)") (class "Default")
      (node (ref "TP7") (pin "P$1") (pinfunction "1_P$1") (pintype "bidirectional"))
      (node (ref "U$40") (pin "13") (pinfunction "VINR_13") (pintype "bidirectional"))
    )
    (net (code "104") (name "Net-(TP8-1)") (class "Default")
      (node (ref "TP8") (pin "P$1") (pinfunction "1_P$1") (pintype "bidirectional"))
      (node (ref "U$40") (pin "28") (pinfunction "SPND_28") (pintype "bidirectional"))
    )
    (net (code "105") (name "Net-(U$1B-MOSI{slash}ADD1)") (class "Default")
      (node (ref "SJ3") (pin "2") (pinfunction "2_2") (pintype "passive"))
      (node (ref "U$1") (pin "032") (pinfunction "MOSI/ADD1_032") (pintype "bidirectional"))
    )
    (net (code "106") (name "Net-(U$1B-SELFBOOT)") (class "Default")
      (node (ref "SJ4") (pin "2") (pinfunction "2_2") (pintype "passive"))
      (node (ref "U$1") (pin "034") (pinfunction "SELFBOOT_034") (pintype "bidirectional"))
    )
    (net (code "107") (name "Net-(U$1B-SS{slash}ADD0)") (class "Default")
      (node (ref "SJ2") (pin "2") (pinfunction "2_2") (pintype "passive"))
      (node (ref "U$1") (pin "033") (pinfunction "SS/ADD0_033") (pintype "bidirectional"))
    )
    (net (code "108") (name "Net-(U$1B-THD_M)") (class "Default")
      (node (ref "U$1") (pin "063") (pinfunction "THD_M_063") (pintype "bidirectional"))
      (node (ref "U$8") (pin "3") (pinfunction "D-_3") (pintype "bidirectional"))
    )
    (net (code "109") (name "Net-(U$1B-THD_P)") (class "Default")
      (node (ref "U$1") (pin "064") (pinfunction "THD_P_064") (pintype "bidirectional"))
      (node (ref "U$8") (pin "2") (pinfunction "D+_2") (pintype "bidirectional"))
    )
    (net (code "110") (name "Net-(U$1B-XTALIN{slash}MCLK)") (class "Default")
      (node (ref "C26") (pin "2") (pinfunction "2_2") (pintype "passive"))
      (node (ref "U$1") (pin "021") (pinfunction "XTALIN/MCLK_021") (pintype "bidirectional"))
      (node (ref "Y1") (pin "2") (pinfunction "2_2") (pintype "passive"))
    )
    (net (code "111") (name "Net-(U$1B-XTALOUT)") (class "Default")
      (node (ref "R3") (pin "2") (pinfunction "2_2") (pintype "passive"))
      (node (ref "U$1") (pin "022") (pinfunction "XTALOUT_022") (pintype "bidirectional"))
    )
    (net (code "112") (name "Net-(U$1E-PLLFILT)") (class "Default")
      (node (ref "C21") (pin "1") (pinfunction "1_1") (pintype "passive"))
      (node (ref "R2") (pin "1") (pinfunction "1_1") (pintype "passive"))
      (node (ref "U$1") (pin "16") (pinfunction "PLLFILT_16") (pintype "bidirectional"))
    )
    (net (code "113") (name "Net-(U$13-PWREN)") (class "Default")
      (node (ref "C29") (pin "+") (pinfunction "+_+") (pintype "passive"))
      (node (ref "U$13") (pin "19") (pinfunction "PWREN_19") (pintype "bidirectional"))
      (node (ref "U$13") (pin "20") (pinfunction "VDD_20") (pintype "bidirectional"))
      (node (ref "U$14") (pin "3") (pinfunction "OUT_3") (pintype "output"))
    )
    (net (code "114") (name "Net-(U$15-AM)") (class "Default")
      (node (ref "C31") (pin "2") (pinfunction "2_2") (pintype "passive"))
      (node (ref "U$15") (pin "4") (pinfunction "AM_4") (pintype "bidirectional"))
    )
    (net (code "115") (name "Net-(U$15-FM)") (class "Default")
      (node (ref "JP15") (pin "2") (pinfunction "2_2") (pintype "passive"))
      (node (ref "U$15") (pin "2") (pinfunction "FM_2") (pintype "bidirectional"))
    )
    (net (code "116") (name "Net-(U$17A-ADC1_L+)") (class "Default")
      (node (ref "C74") (pin "1") (pinfunction "1_1") (pintype "passive"))
      (node (ref "C76") (pin "1") (pinfunction "1_1") (pintype "passive"))
      (node (ref "R34") (pin "1") (pinfunction "1_1") (pintype "passive"))
      (node (ref "U$17") (pin "53") (pinfunction "ADC1_L+_53") (pintype "bidirectional"))
    )
    (net (code "117") (name "Net-(U$17A-ADC1_L-)") (class "Default")
      (node (ref "C75") (pin "2") (pinfunction "2_2") (pintype "passive"))
      (node (ref "C76") (pin "2") (pinfunction "2_2") (pintype "passive"))
      (node (ref "R35") (pin "1") (pinfunction "1_1") (pintype "passive"))
      (node (ref "U$17") (pin "54") (pinfunction "ADC1_L-_54") (pintype "bidirectional"))
    )
    (net (code "118") (name "Net-(U$17A-ADC1_R+)") (class "Default")
      (node (ref "C59") (pin "1") (pinfunction "1_1") (pintype "passive"))
      (node (ref "C77") (pin "1") (pinfunction "1_1") (pintype "passive"))
      (node (ref "R36") (pin "1") (pinfunction "1_1") (pintype "passive"))
      (node (ref "U$17") (pin "55") (pinfunction "ADC1_R+_55") (pintype "bidirectional"))
    )
    (net (code "119") (name "Net-(U$17A-ADC1_R-)") (class "Default")
      (node (ref "C60") (pin "2") (pinfunction "2_2") (pintype "passive"))
      (node (ref "C77") (pin "2") (pinfunction "2_2") (pintype "passive"))
      (node (ref "R37") (pin "1") (pinfunction "1_1") (pintype "passive"))
      (node (ref "U$17") (pin "56") (pinfunction "ADC1_R-_56") (pintype "bidirectional"))
    )
    (net (code "120") (name "Net-(U$17A-ADC2_1-)") (class "Default")
      (node (ref "C96") (pin "2") (pinfunction "2_2") (pintype "passive"))
      (node (ref "C97") (pin "2") (pinfunction "2_2") (pintype "passive"))
      (node (ref "R49") (pin "1") (pinfunction "1_1") (pintype "passive"))
      (node (ref "U$17") (pin "60") (pinfunction "ADC2_1-_60") (pintype "bidirectional"))
    )
    (net (code "121") (name "Net-(U$17A-ADC2_L+)") (class "Default")
      (node (ref "C85") (pin "1") (pinfunction "1_1") (pintype "passive"))
      (node (ref "C87") (pin "1") (pinfunction "1_1") (pintype "passive"))
      (node (ref "R42") (pin "1") (pinfunction "1_1") (pintype "passive"))
      (node (ref "U$17") (pin "57") (pinfunction "ADC2_L+_57") (pintype "bidirectional"))
    )
    (net (code "122") (name "Net-(U$17A-ADC2_L-)") (class "Default")
      (node (ref "C86") (pin "2") (pinfunction "2_2") (pintype "passive"))
      (node (ref "C87") (pin "2") (pinfunction "2_2") (pintype "passive"))
      (node (ref "R43") (pin "1") (pinfunction "1_1") (pintype "passive"))
      (node (ref "U$17") (pin "58") (pinfunction "ADC2_L-_58") (pintype "bidirectional"))
    )
    (net (code "123") (name "Net-(U$17A-ADC2_R+)") (class "Default")
      (node (ref "C95") (pin "1") (pinfunction "1_1") (pintype "passive"))
      (node (ref "C97") (pin "1") (pinfunction "1_1") (pintype "passive"))
      (node (ref "R48") (pin "1") (pinfunction "1_1") (pintype "passive"))
      (node (ref "U$17") (pin "59") (pinfunction "ADC2_R+_59") (pintype "bidirectional"))
    )
    (net (code "124") (name "Net-(U$17B-ADD0)") (class "Default")
      (node (ref "SJ6") (pin "2") (pinfunction "2_2") (pintype "passive"))
      (node (ref "U$17") (pin "30") (pinfunction "ADD0_30") (pintype "bidirectional"))
    )
    (net (code "125") (name "Net-(U$17B-ADD1)") (class "Default")
      (node (ref "SJ5") (pin "2") (pinfunction "2_2") (pintype "passive"))
      (node (ref "U$17") (pin "35") (pinfunction "ADD1_35") (pintype "bidirectional"))
    )
    (net (code "126") (name "Net-(U$17C-DAC2_L+)") (class "Default")
      (node (ref "R25") (pin "2") (pinfunction "2_2") (pintype "passive"))
      (node (ref "U$17") (pin "40") (pinfunction "DAC2_L+_40") (pintype "bidirectional"))
    )
    (net (code "127") (name "Net-(U$17C-DAC2_L-)") (class "Default")
      (node (ref "R24") (pin "2") (pinfunction "2_2") (pintype "passive"))
      (node (ref "U$17") (pin "41") (pinfunction "DAC2_L-_41") (pintype "bidirectional"))
    )
    (net (code "128") (name "Net-(U$17C-DAC2_R+)") (class "Default")
      (node (ref "R23") (pin "2") (pinfunction "2_2") (pintype "passive"))
      (node (ref "U$17") (pin "42") (pinfunction "DAC2_R+_42") (pintype "bidirectional"))
    )
    (net (code "129") (name "Net-(U$17C-DAC2_R-)") (class "Default")
      (node (ref "R22") (pin "2") (pinfunction "2_2") (pintype "passive"))
      (node (ref "U$17") (pin "43") (pinfunction "DAC2_R-_43") (pintype "bidirectional"))
    )
    (net (code "130") (name "Net-(U$17D-CM)") (class "Default")
      (node (ref "C19") (pin "1") (pinfunction "1_1") (pintype "passive"))
      (node (ref "C32") (pin "+") (pinfunction "+_+") (pintype "passive"))
      (node (ref "U$17") (pin "52") (pinfunction "CM_52") (pintype "bidirectional"))
    )
    (net (code "131") (name "Net-(U$35-+)") (class "Default")
      (node (ref "R25") (pin "1") (pinfunction "1_1") (pintype "passive"))
      (node (ref "R26") (pin "2") (pinfunction "2_2") (pintype "passive"))
      (node (ref "U$35") (pin "8") (pinfunction "+_8") (pintype "bidirectional"))
    )
    (net (code "132") (name "Net-(U$35--)") (class "Default")
      (node (ref "R24") (pin "1") (pinfunction "1_1") (pintype "passive"))
      (node (ref "R27") (pin "2") (pinfunction "2_2") (pintype "passive"))
      (node (ref "U$35") (pin "1") (pinfunction "-_1") (pintype "bidirectional"))
    )
    (net (code "133") (name "Net-(U$35-CM)") (class "Default")
      (node (ref "C66") (pin "1") (pinfunction "1_1") (pintype "passive"))
      (node (ref "U$35") (pin "2") (pinfunction "CM_2") (pintype "bidirectional"))
    )
    (net (code "134") (name "Net-(U$35-OUT+)") (class "Default")
      (node (ref "JP8") (pin "1") (pinfunction "1_1") (pintype "passive"))
      (node (ref "R26") (pin "1") (pinfunction "1_1") (pintype "passive"))
      (node (ref "U$35") (pin "4") (pinfunction "OUT+_4") (pintype "bidirectional"))
    )
    (net (code "135") (name "Net-(U$35-OUT-)") (class "Default")
      (node (ref "JP8") (pin "3") (pinfunction "3_3") (pintype "passive"))
      (node (ref "R27") (pin "1") (pinfunction "1_1") (pintype "passive"))
      (node (ref "U$35") (pin "5") (pinfunction "OUT-_5") (pintype "bidirectional"))
    )
    (net (code "136") (name "Net-(U$38-+)") (class "Default")
      (node (ref "R23") (pin "1") (pinfunction "1_1") (pintype "passive"))
      (node (ref "R28") (pin "1") (pinfunction "1_1") (pintype "passive"))
      (node (ref "U$38") (pin "8") (pinfunction "+_8") (pintype "bidirectional"))
    )
    (net (code "137") (name "Net-(U$38--)") (class "Default")
      (node (ref "R22") (pin "1") (pinfunction "1_1") (pintype "passive"))
      (node (ref "R29") (pin "1") (pinfunction "1_1") (pintype "passive"))
      (node (ref "U$38") (pin "1") (pinfunction "-_1") (pintype "bidirectional"))
    )
    (net (code "138") (name "Net-(U$38-CM)") (class "Default")
      (node (ref "C65") (pin "1") (pinfunction "1_1") (pintype "passive"))
      (node (ref "U$38") (pin "2") (pinfunction "CM_2") (pintype "bidirectional"))
    )
    (net (code "139") (name "Net-(U$38-OUT+)") (class "Default")
      (node (ref "JP9") (pin "1") (pinfunction "1_1") (pintype "passive"))
      (node (ref "R28") (pin "2") (pinfunction "2_2") (pintype "passive"))
      (node (ref "U$38") (pin "4") (pinfunction "OUT+_4") (pintype "bidirectional"))
    )
    (net (code "140") (name "Net-(U$38-OUT-)") (class "Default")
      (node (ref "JP9") (pin "3") (pinfunction "3_3") (pintype "passive"))
      (node (ref "R29") (pin "2") (pinfunction "2_2") (pintype "passive"))
      (node (ref "U$38") (pin "5") (pinfunction "OUT-_5") (pintype "bidirectional"))
    )
    (net (code "141") (name "Net-(U$39-+)") (class "Default")
      (node (ref "R30") (pin "2") (pinfunction "2_2") (pintype "passive"))
      (node (ref "R32") (pin "2") (pinfunction "2_2") (pintype "passive"))
      (node (ref "U$39") (pin "8") (pinfunction "+_8") (pintype "bidirectional"))
    )
    (net (code "142") (name "Net-(U$39--)") (class "Default")
      (node (ref "R31") (pin "2") (pinfunction "2_2") (pintype "passive"))
      (node (ref "R33") (pin "2") (pinfunction "2_2") (pintype "passive"))
      (node (ref "U$39") (pin "1") (pinfunction "-_1") (pintype "bidirectional"))
    )
    (net (code "143") (name "Net-(U$39-CM)") (class "Default")
      (node (ref "C67") (pin "1") (pinfunction "1_1") (pintype "passive"))
      (node (ref "U$39") (pin "2") (pinfunction "CM_2") (pintype "bidirectional"))
    )
    (net (code "144") (name "Net-(U$39-OUT+)") (class "Default")
      (node (ref "C72") (pin "+") (pinfunction "+_+") (pintype "passive"))
      (node (ref "R32") (pin "1") (pinfunction "1_1") (pintype "passive"))
      (node (ref "U$39") (pin "4") (pinfunction "OUT+_4") (pintype "bidirectional"))
    )
    (net (code "145") (name "Net-(U$39-OUT-)") (class "Default")
      (node (ref "C73") (pin "+") (pinfunction "+_+") (pintype "passive"))
      (node (ref "R33") (pin "1") (pinfunction "1_1") (pintype "passive"))
      (node (ref "U$39") (pin "5") (pinfunction "OUT-_5") (pintype "bidirectional"))
    )
    (net (code "146") (name "Net-(U$40-D+)") (class "Default")
      (node (ref "R58") (pin "2") (pinfunction "2_2") (pintype "passive"))
      (node (ref "U$40") (pin "1") (pinfunction "D+_1") (pintype "bidirectional"))
    )
    (net (code "147") (name "Net-(U$40-D-)") (class "Default")
      (node (ref "R59") (pin "2") (pinfunction "2_2") (pintype "passive"))
      (node (ref "U$40") (pin "2") (pinfunction "D-_2") (pintype "bidirectional"))
    )
    (net (code "148") (name "Net-(U$40-S{slash}PDIFIN)") (class "Default")
      (node (ref "C115") (pin "2") (pinfunction "2_2") (pintype "passive"))
      (node (ref "U$40") (pin "24") (pinfunction "S/PDIFIN_24") (pintype "bidirectional"))
    )
    (net (code "149") (name "Net-(U$40-S{slash}PDIFOUT)") (class "Default")
      (node (ref "C116") (pin "2") (pinfunction "2_2") (pintype "passive"))
      (node (ref "U$40") (pin "25") (pinfunction "S/PDIFOUT_25") (pintype "bidirectional"))
    )
    (net (code "150") (name "Net-(U$40-XTI)") (class "Default")
      (node (ref "C113") (pin "2") (pinfunction "2_2") (pintype "passive"))
      (node (ref "R61") (pin "2") (pinfunction "2_2") (pintype "passive"))
      (node (ref "U$40") (pin "21") (pinfunction "XTI_21") (pintype "bidirectional"))
      (node (ref "Y2") (pin "2") (pinfunction "2_2") (pintype "passive"))
    )
    (net (code "151") (name "Net-(U$40-XTO)") (class "Default")
      (node (ref "C114") (pin "2") (pinfunction "2_2") (pintype "passive"))
      (node (ref "R61") (pin "1") (pinfunction "1_1") (pintype "passive"))
      (node (ref "U$40") (pin "20") (pinfunction "XTO_20") (pintype "bidirectional"))
      (node (ref "Y2") (pin "1") (pinfunction "1_1") (pintype "passive"))
    )
    (net (code "152") (name "Net-(U$43-B)") (class "Default")
      (node (ref "R54") (pin "2") (pinfunction "2_2") (pintype "passive"))
      (node (ref "R55") (pin "2") (pinfunction "2_2") (pintype "passive"))
      (node (ref "U$43") (pin "2") (pinfunction "B_2") (pintype "bidirectional"))
    )
    (net (code "153") (name "Net-(U$43-Y)") (class "Default")
      (node (ref "R60") (pin "2") (pinfunction "2_2") (pintype "passive"))
      (node (ref "U$43") (pin "4") (pinfunction "Y_4") (pintype "bidirectional"))
    )
    (net (code "154") (name "REG_DRIVE") (class "Default")
      (node (ref "Q1") (pin "1") (pinfunction "B_1") (pintype "passive"))
      (node (ref "R1") (pin "2") (pinfunction "2_2") (pintype "passive"))
      (node (ref "U$1") (pin "3") (pinfunction "VDRIVE_3") (pintype "bidirectional"))
    )
    (net (code "155") (name "RESET") (class "Default")
      (node (ref "U$15") (pin "5") (pinfunction "RST_5") (pintype "bidirectional"))
    )
    (net (code "156") (name "SCL") (class "Default")
      (node (ref "JP6") (pin "4") (pinfunction "4_4") (pintype "passive"))
      (node (ref "U$1") (pin "031") (pinfunction "SCLK/SCL_031") (pintype "bidirectional"))
      (node (ref "U$15") (pin "7") (pinfunction "SCLK_7") (pintype "bidirectional"))
      (node (ref "U$17") (pin "34") (pinfunction "SCL_34") (pintype "bidirectional"))
      (node (ref "U$8") (pin "8") (pinfunction "SCL_8") (pintype "bidirectional"))
    )
    (net (code "157") (name "SDA") (class "Default")
      (node (ref "JP6") (pin "2") (pinfunction "2_2") (pintype "passive"))
      (node (ref "U$1") (pin "030") (pinfunction "MISO/SDA_030") (pintype "bidirectional"))
      (node (ref "U$15") (pin "8") (pinfunction "SDIO_8") (pintype "bidirectional"))
      (node (ref "U$17") (pin "31") (pinfunction "SDA_31") (pintype "bidirectional"))
      (node (ref "U$8") (pin "7") (pinfunction "SDA_7") (pintype "bidirectional"))
    )
    (net (code "158") (name "SPDIF-OUT") (class "Default")
      (node (ref "C115") (pin "1") (pinfunction "1_1") (pintype "passive"))
      (node (ref "U$1") (pin "5") (pinfunction "S/PDIF-OUT_5") (pintype "bidirectional"))
    )
    (net (code "159") (name "SPDIFIN") (class "Default")
      (node (ref "C116") (pin "1") (pinfunction "1_1") (pintype "passive"))
      (node (ref "U$1") (pin "4") (pinfunction "S/PDIF-IN_4") (pintype "bidirectional"))
    )
    (net (code "160") (name "VBUS") (class "Default")
      (node (ref "JP13") (pin "4") (pinfunction "4_4") (pintype "passive"))
      (node (ref "R54") (pin "1") (pinfunction "1_1") (pintype "passive"))
      (node (ref "R57") (pin "2") (pinfunction "2_2") (pintype "passive"))
      (node (ref "U$40") (pin "9") (pinfunction "SEL1_9") (pintype "bidirectional"))
    )
    (net (code "161") (name "VCC") (class "Default")
      (node (ref "C1") (pin "1") (pinfunction "+_1") (pintype "passive"))
      (node (ref "C101") (pin "+") (pinfunction "+_+") (pintype "passive"))
      (node (ref "C102") (pin "+") (pinfunction "+_+") (pintype "passive"))
      (node (ref "C20") (pin "2") (pinfunction "2_2") (pintype "passive"))
      (node (ref "C46") (pin "+") (pinfunction "+_+") (pintype "passive"))
      (node (ref "C50") (pin "1") (pinfunction "1_1") (pintype "passive"))
      (node (ref "C53") (pin "+") (pinfunction "+_+") (pintype "passive"))
      (node (ref "C55") (pin "1") (pinfunction "1_1") (pintype "passive"))
      (node (ref "C62") (pin "2") (pinfunction "2_2") (pintype "passive"))
      (node (ref "C68") (pin "1") (pinfunction "1_1") (pintype "passive"))
      (node (ref "C79") (pin "2") (pinfunction "2_2") (pintype "passive"))
      (node (ref "C89") (pin "2") (pinfunction "2_2") (pintype "passive"))
      (node (ref "C99") (pin "2") (pinfunction "2_2") (pintype "passive"))
      (node (ref "IC2") (pin "8") (pinfunction "V+_8") (pintype "power_in"))
      (node (ref "IC4") (pin "8") (pinfunction "V+_8") (pintype "power_in"))
      (node (ref "IC5") (pin "8") (pinfunction "V+_8") (pintype "power_in"))
      (node (ref "IC6") (pin "8") (pinfunction "V+_8") (pintype "power_in"))
      (node (ref "IC7") (pin "8") (pinfunction "V+_8") (pintype "power_in"))
      (node (ref "JP1") (pin "3") (pinfunction "3_3") (pintype "passive"))
      (node (ref "R63") (pin "1") (pinfunction "1_1") (pintype "passive"))
      (node (ref "U$35") (pin "3") (pinfunction "V+_3") (pintype "bidirectional"))
      (node (ref "U$38") (pin "3") (pinfunction "V+_3") (pintype "bidirectional"))
      (node (ref "U$39") (pin "3") (pinfunction "V+_3") (pintype "bidirectional"))
    )
    (net (code "162") (name "VNEG") (class "Default")
      (node (ref "C100") (pin "1") (pinfunction "1_1") (pintype "passive"))
      (node (ref "C2") (pin "2") (pinfunction "-_2") (pintype "passive"))
      (node (ref "C48") (pin "1") (pinfunction "1_1") (pintype "passive"))
      (node (ref "C49") (pin "1") (pinfunction "1_1") (pintype "passive"))
      (node (ref "C52") (pin "-") (pinfunction "-_-") (pintype "passive"))
      (node (ref "C54") (pin "-") (pinfunction "-_-") (pintype "passive"))
      (node (ref "C56") (pin "2") (pinfunction "2_2") (pintype "passive"))
      (node (ref "C64") (pin "2") (pinfunction "2_2") (pintype "passive"))
      (node (ref "C70") (pin "1") (pinfunction "1_1") (pintype "passive"))
      (node (ref "C80") (pin "1") (pinfunction "1_1") (pintype "passive"))
      (node (ref "C81") (pin "-") (pinfunction "-_-") (pintype "passive"))
      (node (ref "C82") (pin "-") (pinfunction "-_-") (pintype "passive"))
      (node (ref "C90") (pin "1") (pinfunction "1_1") (pintype "passive"))
      (node (ref "IC2") (pin "4") (pinfunction "V-_4") (pintype "power_in"))
      (node (ref "IC4") (pin "4") (pinfunction "V-_4") (pintype "power_in"))
      (node (ref "IC5") (pin "4") (pinfunction "V-_4") (pintype "power_in"))
      (node (ref "IC6") (pin "4") (pinfunction "V-_4") (pintype "power_in"))
      (node (ref "IC7") (pin "4") (pinfunction "V-_4") (pintype "power_in"))
      (node (ref "JP1") (pin "1") (pinfunction "1_1") (pintype "passive"))
      (node (ref "R64") (pin "1") (pinfunction "1_1") (pintype "passive"))
      (node (ref "U$35") (pin "6") (pinfunction "V-_6") (pintype "bidirectional"))
      (node (ref "U$38") (pin "6") (pinfunction "V-_6") (pintype "bidirectional"))
      (node (ref "U$39") (pin "6") (pinfunction "V-_6") (pintype "bidirectional"))
    )
    (net (code "163") (name "unconnected-(U$1A-AUX0-Pad8)") (class "Default")
      (node (ref "U$1") (pin "8") (pinfunction "AUX0_8") (pintype "bidirectional"))
    )
    (net (code "164") (name "unconnected-(U$1A-AUX1-Pad9)") (class "Default")
      (node (ref "U$1") (pin "9") (pinfunction "AUX1_9") (pintype "bidirectional"))
    )
    (net (code "165") (name "unconnected-(U$1A-AUX2-Pad10)") (class "Default")
      (node (ref "U$1") (pin "10") (pinfunction "AUX2_10") (pintype "bidirectional"))
    )
    (net (code "166") (name "unconnected-(U$1A-AUX3-Pad11)") (class "Default")
      (node (ref "U$1") (pin "11") (pinfunction "AUX3_11") (pintype "bidirectional"))
    )
    (net (code "167") (name "unconnected-(U$1A-AUX4-Pad12)") (class "Default")
      (node (ref "U$1") (pin "12") (pinfunction "AUX4_12") (pintype "bidirectional"))
    )
    (net (code "168") (name "unconnected-(U$1A-AUX5-Pad13)") (class "Default")
      (node (ref "U$1") (pin "13") (pinfunction "AUX5_13") (pintype "bidirectional"))
    )
    (net (code "169") (name "unconnected-(U$1B-MOSI_M-Pad027)") (class "Default")
      (node (ref "U$1") (pin "027") (pinfunction "MOSI_M_027") (pintype "bidirectional"))
    )
    (net (code "170") (name "unconnected-(U$1B-MP6-Pad045)") (class "Default")
      (node (ref "U$1") (pin "045") (pinfunction "MP6_045") (pintype "bidirectional"))
    )
    (net (code "171") (name "unconnected-(U$1B-MP7-Pad046)") (class "Default")
      (node (ref "U$1") (pin "046") (pinfunction "MP7_046") (pintype "bidirectional"))
    )
    (net (code "172") (name "unconnected-(U$1B-SCL_M{slash}SCLK_M-Pad028)") (class "Default")
      (node (ref "U$1") (pin "028") (pinfunction "SCL_M/SCLK_M_028") (pintype "bidirectional"))
    )
    (net (code "173") (name "unconnected-(U$1B-SDA_M{slash}MISO_M-Pad029)") (class "Default")
      (node (ref "U$1") (pin "029") (pinfunction "SDA_M/MISO_M_029") (pintype "bidirectional"))
    )
    (net (code "174") (name "unconnected-(U$1B-SS_M-Pad026)") (class "Default")
      (node (ref "U$1") (pin "026") (pinfunction "SS_M_026") (pintype "bidirectional"))
    )
    (net (code "175") (name "unconnected-(U$8-ALT-Pad6)") (class "Default")
      (node (ref "U$8") (pin "6") (pinfunction "ALT_6") (pintype "bidirectional"))
    )
    (net (code "176") (name "unconnected-(U$8-THRM-Pad4)") (class "Default")
      (node (ref "U$8") (pin "4") (pinfunction "THRM_4") (pintype "bidirectional"))
    )
    (net (code "177") (name "unconnected-(U$13-AIC0-Pad3)") (class "Default")
      (node (ref "U$13") (pin "3") (pinfunction "AIC0_3") (pintype "bidirectional"))
    )
    (net (code "178") (name "unconnected-(U$13-GPIO2-Pad2)") (class "Default")
      (node (ref "U$13") (pin "2") (pinfunction "GPIO2_2") (pintype "bidirectional"))
    )
    (net (code "179") (name "unconnected-(U$13-GPIO3-Pad1)") (class "Default")
      (node (ref "U$13") (pin "1") (pinfunction "GPIO3_1") (pintype "bidirectional"))
    )
    (net (code "180") (name "unconnected-(U$13-GPIO4-Pad4)") (class "Default")
      (node (ref "U$13") (pin "4") (pinfunction "GPIO4_4") (pintype "bidirectional"))
    )
    (net (code "181") (name "unconnected-(U$13-GPIO5-Pad5)") (class "Default")
      (node (ref "U$13") (pin "5") (pinfunction "GPIO5_5") (pintype "bidirectional"))
    )
    (net (code "182") (name "unconnected-(U$13-GPIO6-Pad18)") (class "Default")
      (node (ref "U$13") (pin "18") (pinfunction "GPIO6_18") (pintype "bidirectional"))
    )
    (net (code "183") (name "unconnected-(U$13-GPIO7-Pad17)") (class "Default")
      (node (ref "U$13") (pin "17") (pinfunction "GPIO7_17") (pintype "bidirectional"))
    )
    (net (code "184") (name "unconnected-(U$13-GPIO9-Pad10)") (class "Default")
      (node (ref "U$13") (pin "10") (pinfunction "GPIO9_10") (pintype "bidirectional"))
    )
    (net (code "185") (name "unconnected-(U$13-GPIO10-Pad9)") (class "Default")
      (node (ref "U$13") (pin "9") (pinfunction "GPIO10_9") (pintype "bidirectional"))
    )
    (net (code "186") (name "unconnected-(U$13-GPIO11-Pad8)") (class "Default")
      (node (ref "U$13") (pin "8") (pinfunction "GPIO11_8") (pintype "bidirectional"))
    )
    (net (code "187") (name "unconnected-(U$13-GPIO12-Pad6)") (class "Default")
      (node (ref "U$13") (pin "6") (pinfunction "GPIO12_6") (pintype "bidirectional"))
    )
    (net (code "188") (name "unconnected-(U$13-GPIO13-Pad7)") (class "Default")
      (node (ref "U$13") (pin "7") (pinfunction "GPIO13_7") (pintype "bidirectional"))
    )
    (net (code "189") (name "unconnected-(U$13-LED0-Pad30)") (class "Default")
      (node (ref "U$13") (pin "30") (pinfunction "LED0_30") (pintype "bidirectional"))
    )
    (net (code "190") (name "unconnected-(U$13-LED1-Pad29)") (class "Default")
      (node (ref "U$13") (pin "29") (pinfunction "LED1_29") (pintype "bidirectional"))
    )
    (net (code "191") (name "unconnected-(U$13-MIC_BIAS-Pad31)") (class "Default")
      (node (ref "U$13") (pin "31") (pinfunction "MIC_BIAS_31") (pintype "bidirectional"))
    )
    (net (code "192") (name "unconnected-(U$13-MIC_L+-Pad32)") (class "Default")
      (node (ref "U$13") (pin "32") (pinfunction "MIC_L+_32") (pintype "bidirectional"))
    )
    (net (code "193") (name "unconnected-(U$13-MIC_L--Pad34)") (class "Default")
      (node (ref "U$13") (pin "34") (pinfunction "MIC_L-_34") (pintype "bidirectional"))
    )
    (net (code "194") (name "unconnected-(U$13-MIC_R+-Pad33)") (class "Default")
      (node (ref "U$13") (pin "33") (pinfunction "MIC_R+_33") (pintype "bidirectional"))
    )
    (net (code "195") (name "unconnected-(U$13-MIC_R--Pad35)") (class "Default")
      (node (ref "U$13") (pin "35") (pinfunction "MIC_R-_35") (pintype "bidirectional"))
    )
    (net (code "196") (name "unconnected-(U$13-SPI_CLK-Pad27)") (class "Default")
      (node (ref "U$13") (pin "27") (pinfunction "SPI_CLK_27") (pintype "bidirectional"))
    )
    (net (code "197") (name "unconnected-(U$13-SPI_MISO-Pad26)") (class "Default")
      (node (ref "U$13") (pin "26") (pinfunction "SPI_MISO_26") (pintype "bidirectional"))
    )
    (net (code "198") (name "unconnected-(U$13-SPI_MOSI-Pad28)") (class "Default")
      (node (ref "U$13") (pin "28") (pinfunction "SPI_MOSI_28") (pintype "bidirectional"))
    )
    (net (code "199") (name "unconnected-(U$13-SPI_SS-Pad25)") (class "Default")
      (node (ref "U$13") (pin "25") (pinfunction "SPI_SS_25") (pintype "bidirectional"))
    )
    (net (code "200") (name "unconnected-(U$13-SPKR_L+-Pad40)") (class "Default")
      (node (ref "U$13") (pin "40") (pinfunction "SPKR_L+_40") (pintype "bidirectional"))
    )
    (net (code "201") (name "unconnected-(U$13-SPKR_L--Pad38)") (class "Default")
      (node (ref "U$13") (pin "38") (pinfunction "SPKR_L-_38") (pintype "bidirectional"))
    )
    (net (code "202") (name "unconnected-(U$13-SPKR_R+-Pad39)") (class "Default")
      (node (ref "U$13") (pin "39") (pinfunction "SPKR_R+_39") (pintype "bidirectional"))
    )
    (net (code "203") (name "unconnected-(U$13-SPKR_R--Pad37)") (class "Default")
      (node (ref "U$13") (pin "37") (pinfunction "SPKR_R-_37") (pintype "bidirectional"))
    )
    (net (code "204") (name "unconnected-(U$13-USBD+-Pad12)") (class "Default")
      (node (ref "U$13") (pin "12") (pinfunction "USBD+_12") (pintype "bidirectional"))
    )
    (net (code "205") (name "unconnected-(U$13-USBD--Pad11)") (class "Default")
      (node (ref "U$13") (pin "11") (pinfunction "USBD-_11") (pintype "bidirectional"))
    )
    (net (code "206") (name "unconnected-(U$15-CLK-Pad9)") (class "Default")
      (node (ref "U$15") (pin "9") (pinfunction "CLK_9") (pintype "bidirectional"))
    )
    (net (code "207") (name "unconnected-(U$15-SEN-Pad6)") (class "Default")
      (node (ref "U$15") (pin "6") (pinfunction "SEN_6") (pintype "bidirectional"))
    )
    (net (code "208") (name "unconnected-(U$17A-DATAOUT1-Pad26)") (class "Default")
      (node (ref "U$17") (pin "26") (pinfunction "DATAOUT1_26") (pintype "bidirectional"))
    )
    (net (code "209") (name "unconnected-(U$17B-MCLK-OUT-Pad3)") (class "Default")
      (node (ref "U$17") (pin "3") (pinfunction "MCLK-OUT_3") (pintype "bidirectional"))
    )
    (net (code "210") (name "unconnected-(U$17C-DAC1_L+-Pad36)") (class "Default")
      (node (ref "U$17") (pin "36") (pinfunction "DAC1_L+_36") (pintype "bidirectional"))
    )
    (net (code "211") (name "unconnected-(U$17C-DAC1_L--Pad37)") (class "Default")
      (node (ref "U$17") (pin "37") (pinfunction "DAC1_L-_37") (pintype "bidirectional"))
    )
    (net (code "212") (name "unconnected-(U$17C-DAC1_R+-Pad38)") (class "Default")
      (node (ref "U$17") (pin "38") (pinfunction "DAC1_R+_38") (pintype "bidirectional"))
    )
    (net (code "213") (name "unconnected-(U$17C-DAC1_R--Pad39)") (class "Default")
      (node (ref "U$17") (pin "39") (pinfunction "DAC1_R-_39") (pintype "bidirectional"))
    )
    (net (code "214") (name "unconnected-(U$17C-DATAIN1-Pad19)") (class "Default")
      (node (ref "U$17") (pin "19") (pinfunction "DATAIN1_19") (pintype "bidirectional"))
    )
    (net (code "215") (name "unconnected-(U$17C-DATAIN2-Pad18)") (class "Default")
      (node (ref "U$17") (pin "18") (pinfunction "DATAIN2_18") (pintype "bidirectional"))
    )
    (net (code "216") (name "unconnected-(U$17C-DATAIN3-Pad15)") (class "Default")
      (node (ref "U$17") (pin "15") (pinfunction "DATAIN3_15") (pintype "bidirectional"))
    )
    (net (code "217") (name "unconnected-(U$40-HID0-Pad5)") (class "Default")
      (node (ref "U$40") (pin "5") (pinfunction "HID0_5") (pintype "bidirectional"))
    )
    (net (code "218") (name "unconnected-(U$40-HID1-Pad6)") (class "Default")
      (node (ref "U$40") (pin "6") (pinfunction "HID1_6") (pintype "bidirectional"))
    )
    (net (code "219") (name "unconnected-(U$40-HID2-Pad7)") (class "Default")
      (node (ref "U$40") (pin "7") (pinfunction "HID2_7") (pintype "bidirectional"))
    )
    (net (code "220") (name "~{RESET}") (class "Default")
      (node (ref "R62") (pin "1") (pinfunction "1_1") (pintype "passive"))
      (node (ref "S1") (pin "1") (pinfunction "1_1") (pintype "passive"))
      (node (ref "S1") (pin "2") (pinfunction "2_2") (pintype "passive"))
      (node (ref "U$1") (pin "024") (pinfunction "RESET_024") (pintype "bidirectional"))
      (node (ref "U$17") (pin "14") (pinfunction "~{RESET}_14") (pintype "bidirectional"))
      (node (ref "U$52") (pin "2") (pinfunction "~{RST}_2") (pintype "bidirectional"))
    )
  )
)
